# SCH_Octoslime_2022-08-05.net
KiCad netlist of a schematic drawn in EasyEDA
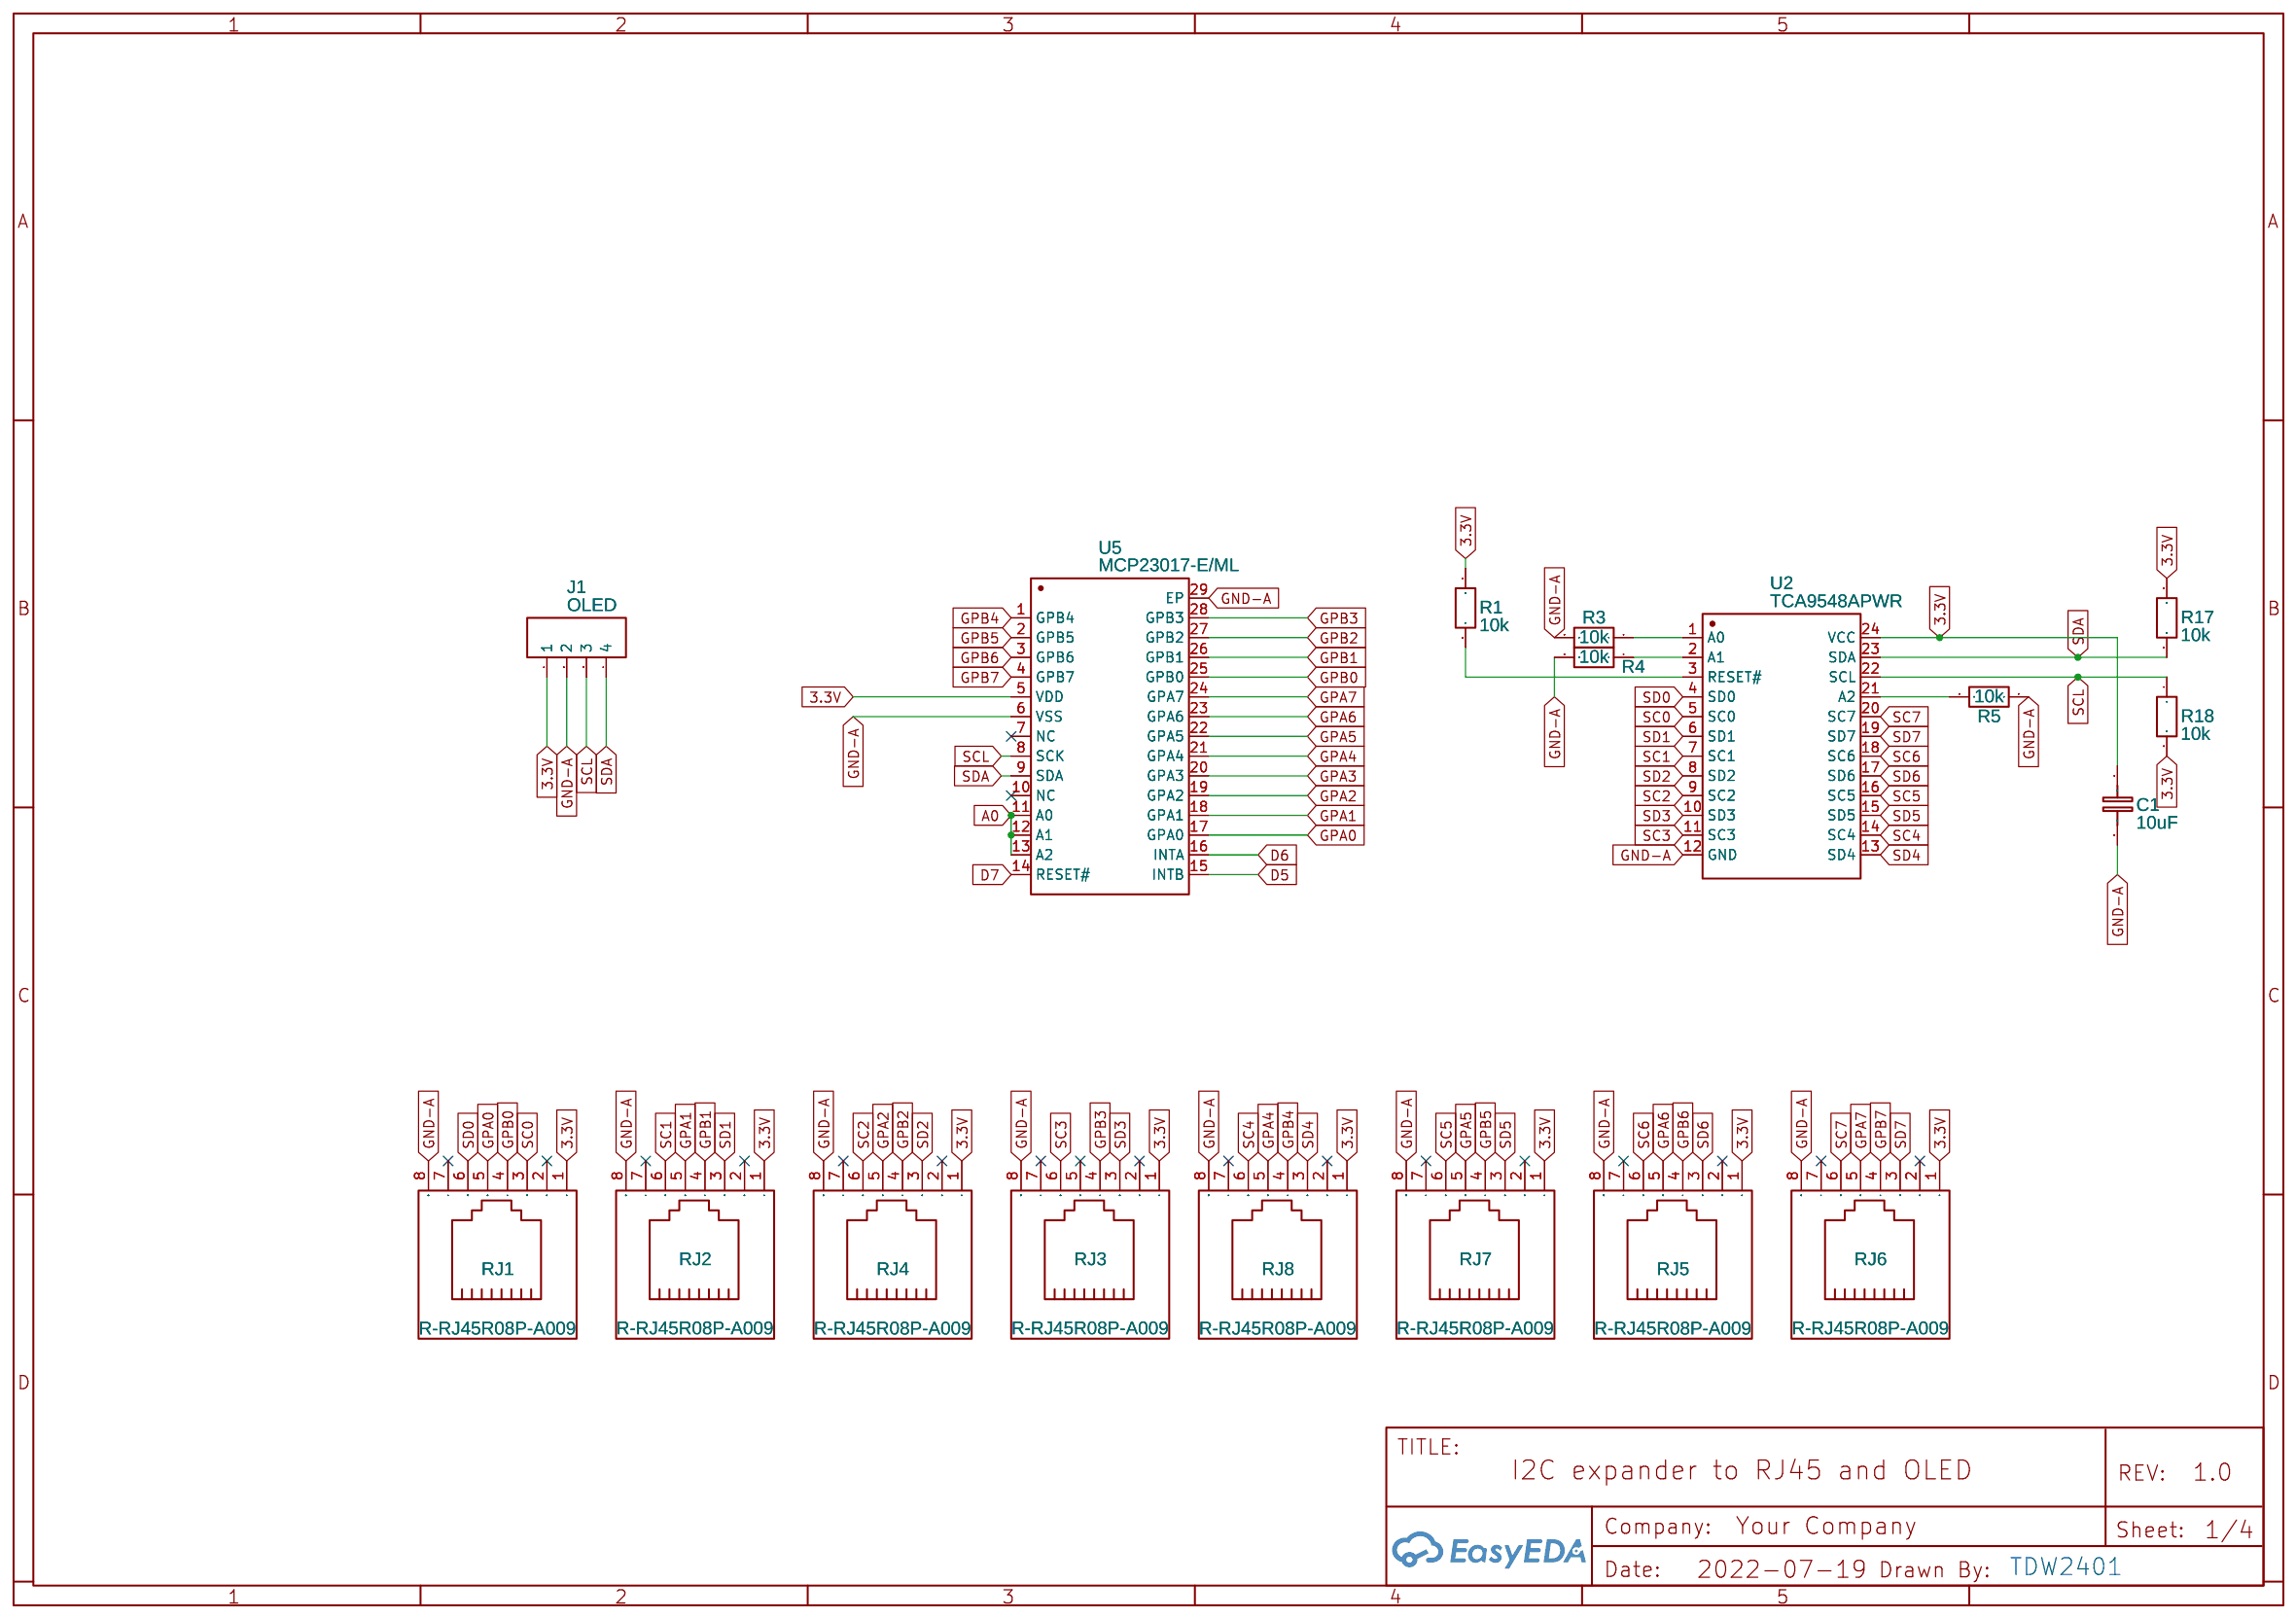
[diagram p0: I2C breakout and OLED]
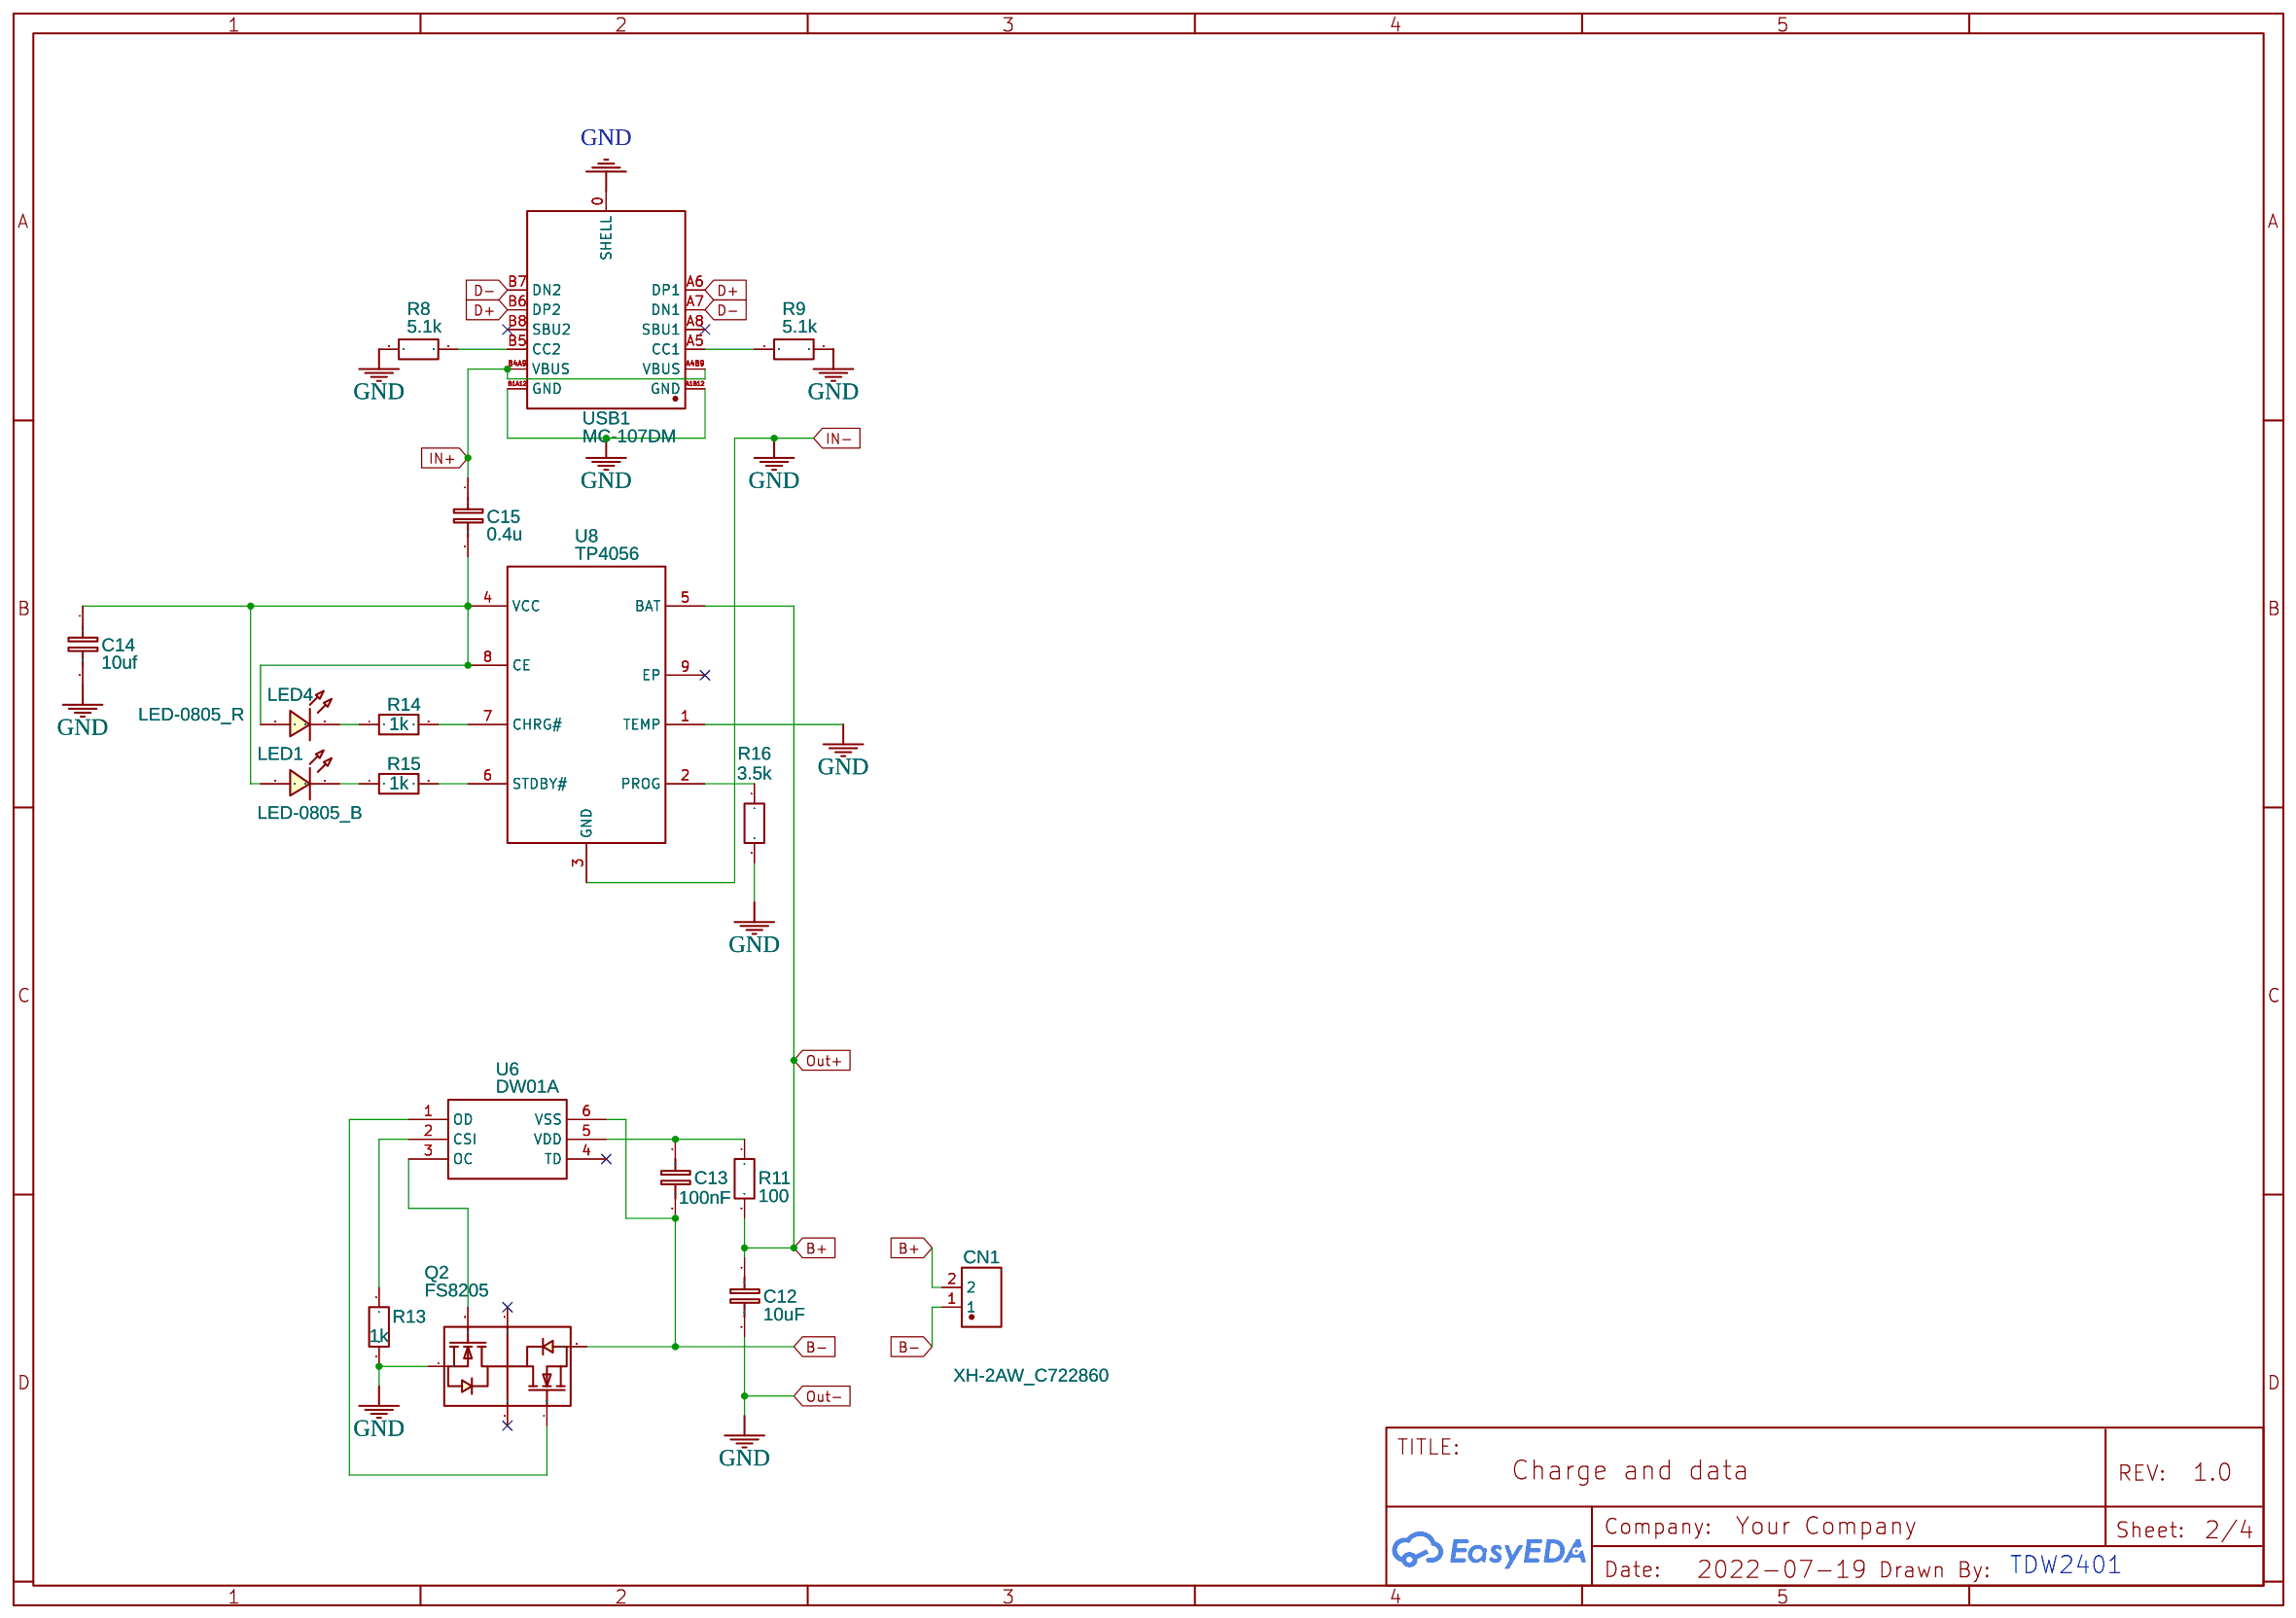
[diagram p1: Charge / data]
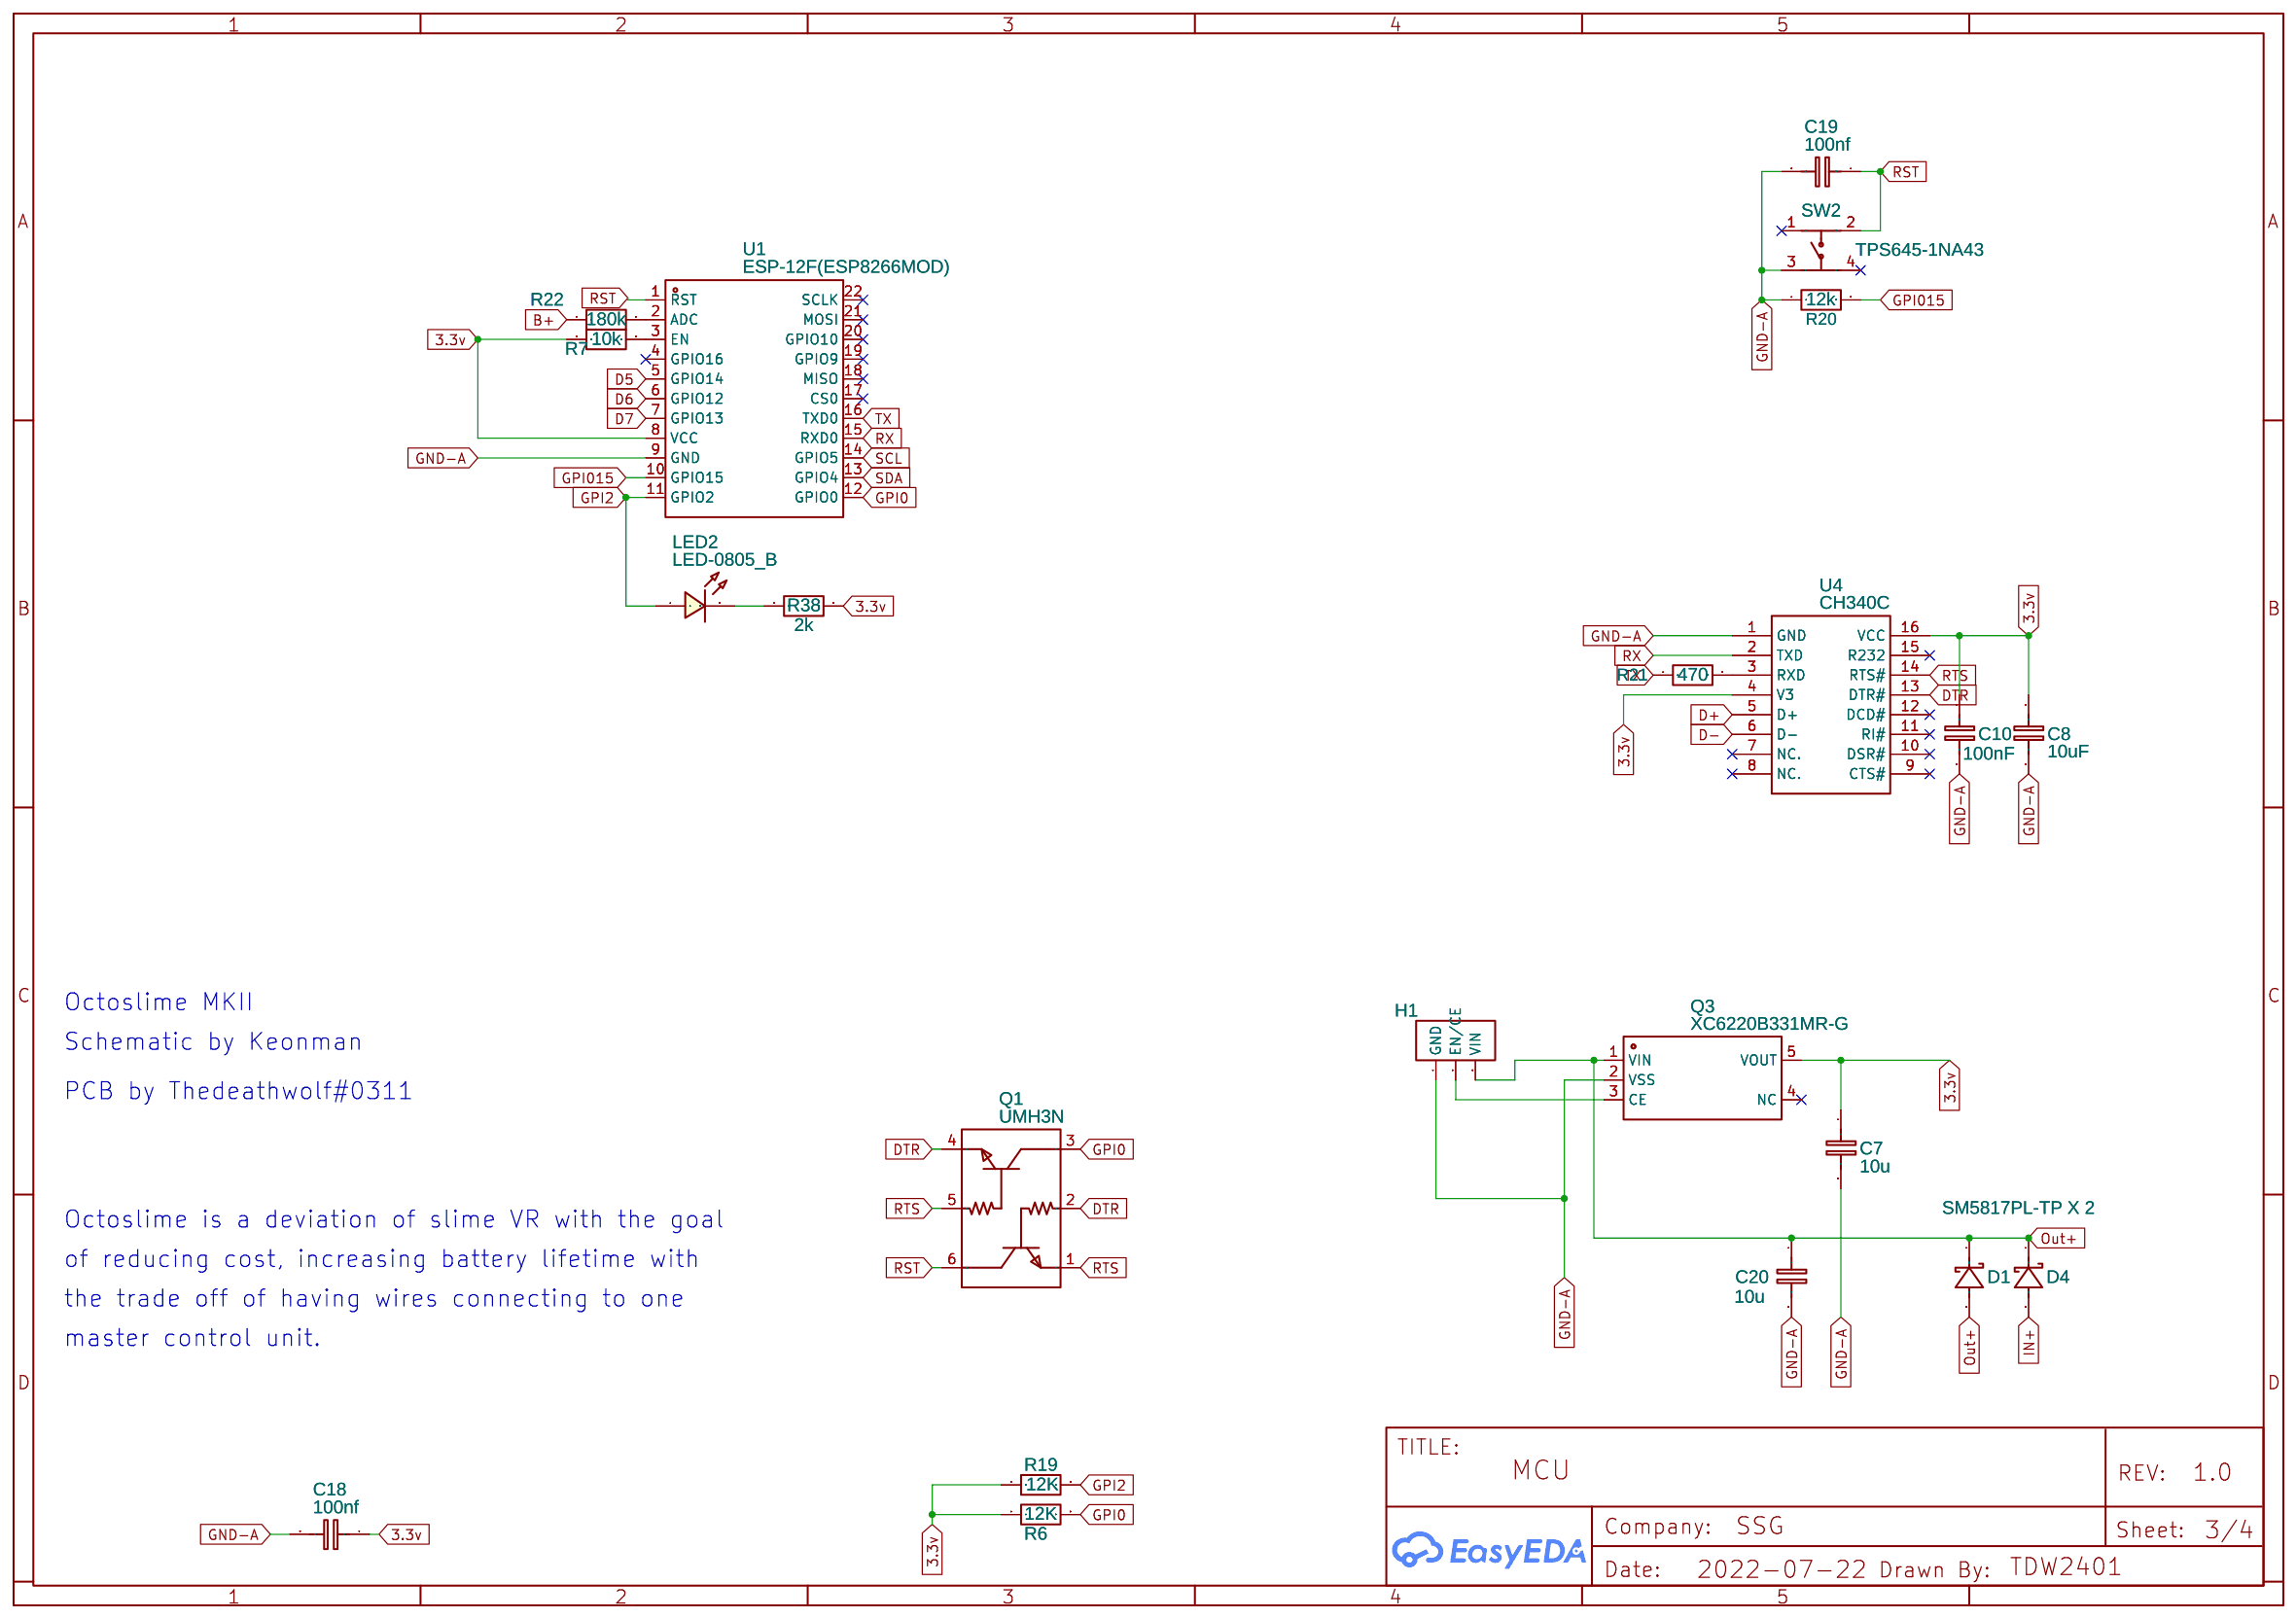
[diagram p2: MCU]
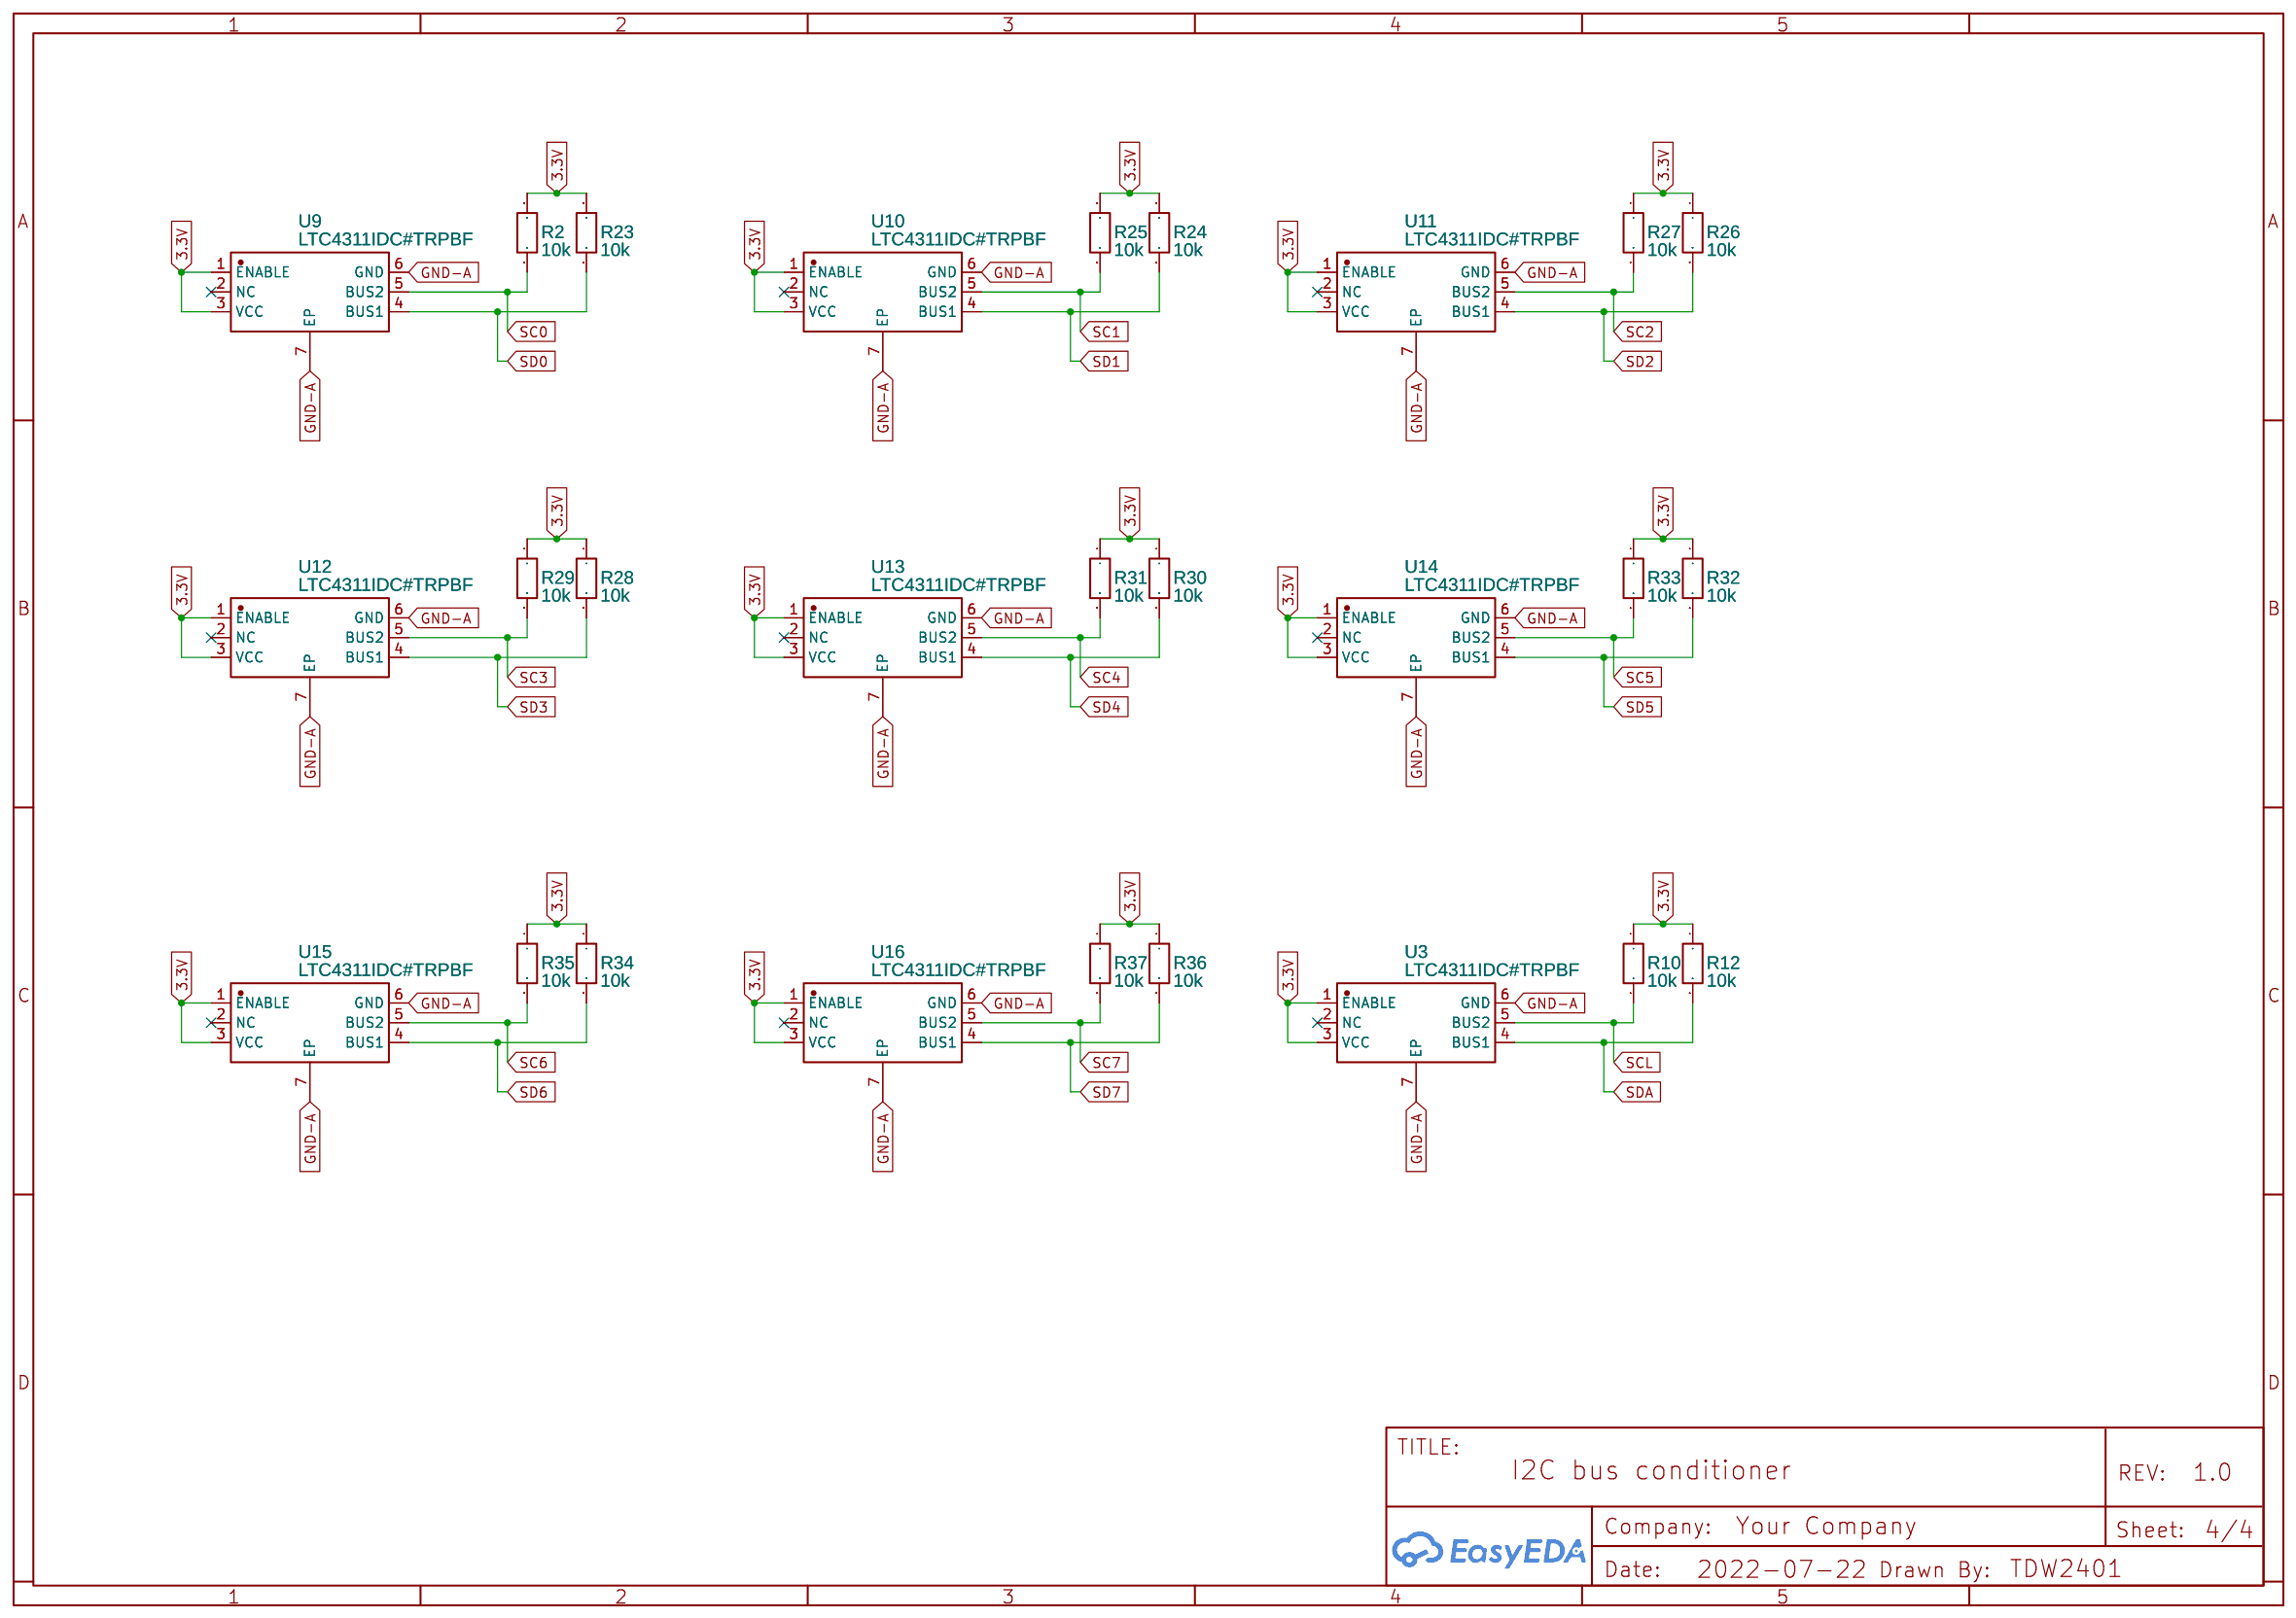
[diagram p3: I2C thing - ma - jigXC6220B331PR-G]

(export (version "E")
  (design (tool "Eeschema 10.0.6"))
  (components
    (comp (ref "C1") (value "10uF") (libsource (lib "") (part "C_0805_EU")))
    (comp (ref "J1")
      (value "OLED")
      (fields (field (name "BOM_Supplier Part") "C124378"))
      (libsource (lib "") (part "HDR-M-2.54_1x4"))
    )
    (comp (ref "R1") (value "10k") (libsource (lib "") (part "R_0805_EU")))
    (comp (ref "R3") (value "10k") (libsource (lib "") (part "R_0805_EU_1")))
    (comp (ref "R4") (value "10k") (libsource (lib "") (part "R_0805_EU_1")))
    (comp (ref "R5") (value "10k") (libsource (lib "") (part "R_0805_EU_1")))
    (comp (ref "R17") (value "10k") (libsource (lib "") (part "R_0805_EU")))
    (comp (ref "R18") (value "10k") (libsource (lib "") (part "R_0805_EU")))
    (comp (ref "RJ1")
      (value "R-RJ45R08P-A009")
      (fields (field (name "BOM_Supplier Part") "C2902700"))
      (libsource (lib "") (part "R-RJ45R08P-A009"))
    )
    (comp (ref "RJ2")
      (value "R-RJ45R08P-A009")
      (fields (field (name "BOM_Supplier Part") "C2902700"))
      (libsource (lib "") (part "R-RJ45R08P-A009"))
    )
    (comp (ref "RJ3")
      (value "R-RJ45R08P-A009")
      (fields (field (name "BOM_Supplier Part") "C2902700"))
      (libsource (lib "") (part "R-RJ45R08P-A009"))
    )
    (comp (ref "RJ4")
      (value "R-RJ45R08P-A009")
      (fields (field (name "BOM_Supplier Part") "C2902700"))
      (libsource (lib "") (part "R-RJ45R08P-A009"))
    )
    (comp (ref "RJ5")
      (value "R-RJ45R08P-A009")
      (fields (field (name "BOM_Supplier Part") "C2902700"))
      (libsource (lib "") (part "R-RJ45R08P-A009"))
    )
    (comp (ref "RJ6")
      (value "R-RJ45R08P-A009")
      (fields (field (name "BOM_Supplier Part") "C2902700"))
      (libsource (lib "") (part "R-RJ45R08P-A009"))
    )
    (comp (ref "RJ7")
      (value "R-RJ45R08P-A009")
      (fields (field (name "BOM_Supplier Part") "C2902700"))
      (libsource (lib "") (part "R-RJ45R08P-A009"))
    )
    (comp (ref "RJ8")
      (value "R-RJ45R08P-A009")
      (fields (field (name "BOM_Supplier Part") "C2902700"))
      (libsource (lib "") (part "R-RJ45R08P-A009"))
    )
    (comp (ref "U2")
      (value "TCA9548APWR")
      (fields (field (name "BOM_Supplier Part") "C130026"))
      (libsource (lib "") (part "TCA9548APWR"))
    )
    (comp (ref "U5")
      (value "MCP23017-E/ML")
      (fields (field (name "BOM_Supplier Part") "C639770"))
      (libsource (lib "") (part "MCP23017-E/ML"))
    )
    (comp (ref "C12") (value "10uF") (libsource (lib "") (part "C_0805_EU_1")))
    (comp (ref "C13") (value "100nF") (libsource (lib "") (part "C_0805_EU_1")))
    (comp (ref "C14") (value "10uf") (libsource (lib "") (part "C_0805_EU")))
    (comp (ref "C15") (value "0.4u") (libsource (lib "") (part "C_0805_EU_2")))
    (comp (ref "CN1")
      (value "XH-2AW_C722860")
      (fields (field (name "BOM_Manufacturer Part") "XH-2AW") (field (name "BOM_Supplier Part") "C722860"))
      (libsource (lib "") (part "XH-2AW_C722860"))
    )
    (comp (ref "LED1")
      (value "LED-0805_B")
      (fields
        (field (name "BOM_Manufacturer Part") "D-B080508B1-KS2")
        (field (name "BOM_Supplier Part") "C108412")
      )
      (libsource (lib "") (part "LED-0805_B"))
    )
    (comp (ref "LED4")
      (value "LED-0805_R")
      (fields
        (field (name "BOM_Manufacturer Part") "17-21SURC/S530-A3/TR8")
        (field (name "BOM_Supplier Part") "C72037")
      )
      (libsource (lib "") (part "LED-0805_R"))
    )
    (comp (ref "Q2")
      (value "FS8205")
      (fields (field (name "BOM_Supplier Part") "C32254"))
      (libsource (lib "") (part "FS8205"))
    )
    (comp (ref "R8") (value "5.1k") (libsource (lib "") (part "R_0805_EU_1")))
    (comp (ref "R9") (value "5.1k") (libsource (lib "") (part "R_0805_EU_1")))
    (comp (ref "R11") (value "100") (libsource (lib "") (part "R_0805_EU")))
    (comp (ref "R13") (value "1k") (libsource (lib "") (part "R_0805_EU")))
    (comp (ref "R14") (value "1k") (libsource (lib "") (part "R_0805_EU_1")))
    (comp (ref "R15") (value "1k") (libsource (lib "") (part "R_0805_EU_1")))
    (comp (ref "R16") (value "3.5k") (libsource (lib "") (part "R_0805_EU")))
    (comp (ref "U6")
      (value "DW01A")
      (fields (field (name "BOM_Supplier Part") "C85680"))
      (libsource (lib "") (part "DW01A"))
    )
    (comp (ref "U8")
      (value "TP4056")
      (fields (field (name "BOM_Supplier Part") "C16581"))
      (libsource (lib "") (part "TP4056"))
    )
    (comp (ref "USB1")
      (value "MC-107DM")
      (fields (field (name "BOM_Supplier Part") "C2874569"))
      (libsource (lib "") (part "MC-107DM"))
    )
    (comp (ref "C7") (value "10u") (libsource (lib "") (part "C_0805_EU")))
    (comp (ref "C8") (value "10uF") (libsource (lib "") (part "C_0805_EU")))
    (comp (ref "C10") (value "100nF") (libsource (lib "") (part "C_0805_EU")))
    (comp (ref "C18") (value "100nf") (libsource (lib "") (part "C_0805_EU_2")))
    (comp (ref "C19") (value "100nf") (libsource (lib "") (part "C_0805_EU_1")))
    (comp (ref "C20") (value "10u") (libsource (lib "") (part "C_0805_EU")))
    (comp (ref "D1")
      (value "SM5817PL-TP X 2")
      (fields
        (field (name "BOM_Manufacturer Part") "SM5817PL-TP")
        (field (name "BOM_Supplier Part") "C669022")
      )
      (libsource (lib "") (part "SM5817PL-TP"))
    )
    (comp (ref "D4")
      (value "SM5817PL-TP X 2")
      (fields
        (field (name "BOM_Manufacturer Part") "SM5817PL-TP")
        (field (name "BOM_Supplier Part") "C669022")
      )
      (libsource (lib "") (part "SM5817PL-TP"))
    )
    (comp (ref "H1")
      (value "HDR-F-2.54_1x3")
      (fields (field (name "BOM_Supplier Part") "C146690"))
      (libsource (lib "") (part "HDR-F-2.54_1x3"))
    )
    (comp (ref "LED2")
      (value "LED-0805_B")
      (fields
        (field (name "BOM_Manufacturer Part") "D-B080508B1-KS2")
        (field (name "BOM_Supplier Part") "C108412")
      )
      (libsource (lib "") (part "LED-0805_B"))
    )
    (comp (ref "Q1")
      (value "UMH3N")
      (fields (field (name "BOM_Supplier Part") "C62892"))
      (libsource (lib "") (part "UMH3N"))
    )
    (comp (ref "Q3")
      (value "XC6220B331MR-G")
      (fields (field (name "BOM_Supplier Part") "C86534"))
      (libsource (lib "") (part "XC6220B331MR-G"))
    )
    (comp (ref "R6") (value "12K") (libsource (lib "") (part "R_0805_EU")))
    (comp (ref "R7") (value "10k") (libsource (lib "") (part "R_0805_EU")))
    (comp (ref "R19") (value "12K") (libsource (lib "") (part "R_0805_EU")))
    (comp (ref "R20") (value "12k") (libsource (lib "") (part "R_0805_EU")))
    (comp (ref "R21") (value "470") (libsource (lib "") (part "R_0805_EU")))
    (comp (ref "R22") (value "180k") (libsource (lib "") (part "R_0805_EU")))
    (comp (ref "R38") (value "2k") (libsource (lib "") (part "R_0805_EU")))
    (comp (ref "SW2")
      (value "TPS645-1NA43")
      (fields (field (name "BOM_Supplier Part") "C2828575"))
      (libsource (lib "") (part "TPS645-1NA43"))
    )
    (comp (ref "U1")
      (value "ESP-12F(ESP8266MOD)")
      (fields (field (name "BOM_Supplier Part") "C82891"))
      (libsource (lib "") (part "ESP-12F(ESP8266MOD)"))
    )
    (comp (ref "U4")
      (value "CH340C")
      (fields (field (name "BOM_Supplier Part") "C84681"))
      (libsource (lib "") (part "CH340C"))
    )
    (comp (ref "R2") (value "10k") (libsource (lib "") (part "R_0805_EU")))
    (comp (ref "R10") (value "10k") (libsource (lib "") (part "R_0805_EU")))
    (comp (ref "R12") (value "10k") (libsource (lib "") (part "R_0805_EU")))
    (comp (ref "R23") (value "10k") (libsource (lib "") (part "R_0805_EU")))
    (comp (ref "R24") (value "10k") (libsource (lib "") (part "R_0805_EU")))
    (comp (ref "R25") (value "10k") (libsource (lib "") (part "R_0805_EU")))
    (comp (ref "R26") (value "10k") (libsource (lib "") (part "R_0805_EU")))
    (comp (ref "R27") (value "10k") (libsource (lib "") (part "R_0805_EU")))
    (comp (ref "R28") (value "10k") (libsource (lib "") (part "R_0805_EU")))
    (comp (ref "R29") (value "10k") (libsource (lib "") (part "R_0805_EU")))
    (comp (ref "R30") (value "10k") (libsource (lib "") (part "R_0805_EU")))
    (comp (ref "R31") (value "10k") (libsource (lib "") (part "R_0805_EU")))
    (comp (ref "R32") (value "10k") (libsource (lib "") (part "R_0805_EU")))
    (comp (ref "R33") (value "10k") (libsource (lib "") (part "R_0805_EU")))
    (comp (ref "R34") (value "10k") (libsource (lib "") (part "R_0805_EU")))
    (comp (ref "R35") (value "10k") (libsource (lib "") (part "R_0805_EU")))
    (comp (ref "R36") (value "10k") (libsource (lib "") (part "R_0805_EU")))
    (comp (ref "R37") (value "10k") (libsource (lib "") (part "R_0805_EU")))
    (comp (ref "U3")
      (value "LTC4311IDC#TRPBF")
      (fields (field (name "BOM_Supplier Part") "C688096"))
      (libsource (lib "") (part "LTC4311IDC#TRPBF"))
    )
    (comp (ref "U9")
      (value "LTC4311IDC#TRPBF")
      (fields (field (name "BOM_Supplier Part") "C688096"))
      (libsource (lib "") (part "LTC4311IDC#TRPBF"))
    )
    (comp (ref "U10")
      (value "LTC4311IDC#TRPBF")
      (fields (field (name "BOM_Supplier Part") "C688096"))
      (libsource (lib "") (part "LTC4311IDC#TRPBF"))
    )
    (comp (ref "U11")
      (value "LTC4311IDC#TRPBF")
      (fields (field (name "BOM_Supplier Part") "C688096"))
      (libsource (lib "") (part "LTC4311IDC#TRPBF"))
    )
    (comp (ref "U12")
      (value "LTC4311IDC#TRPBF")
      (fields (field (name "BOM_Supplier Part") "C688096"))
      (libsource (lib "") (part "LTC4311IDC#TRPBF"))
    )
    (comp (ref "U13")
      (value "LTC4311IDC#TRPBF")
      (fields (field (name "BOM_Supplier Part") "C688096"))
      (libsource (lib "") (part "LTC4311IDC#TRPBF"))
    )
    (comp (ref "U14")
      (value "LTC4311IDC#TRPBF")
      (fields (field (name "BOM_Supplier Part") "C688096"))
      (libsource (lib "") (part "LTC4311IDC#TRPBF"))
    )
    (comp (ref "U15")
      (value "LTC4311IDC#TRPBF")
      (fields (field (name "BOM_Supplier Part") "C688096"))
      (libsource (lib "") (part "LTC4311IDC#TRPBF"))
    )
    (comp (ref "U16")
      (value "LTC4311IDC#TRPBF")
      (fields (field (name "BOM_Supplier Part") "C688096"))
      (libsource (lib "") (part "LTC4311IDC#TRPBF"))
    )
  )
  (nets
    (net (code "1") (name "3.3V") (class "Default")
      (node (ref "C1") (pin "1") (pinfunction "1_1") (pintype "unspecified"))
      (node (ref "J1") (pin "1") (pinfunction "1_1") (pintype "unspecified"))
      (node (ref "R1") (pin "1") (pinfunction "1_1") (pintype "unspecified"))
      (node (ref "R10") (pin "1") (pinfunction "1_1") (pintype "unspecified"))
      (node (ref "R12") (pin "1") (pinfunction "1_1") (pintype "unspecified"))
      (node (ref "R17") (pin "1") (pinfunction "1_1") (pintype "unspecified"))
      (node (ref "R18") (pin "2") (pinfunction "2_2") (pintype "unspecified"))
      (node (ref "R2") (pin "1") (pinfunction "1_1") (pintype "unspecified"))
      (node (ref "R23") (pin "1") (pinfunction "1_1") (pintype "unspecified"))
      (node (ref "R24") (pin "1") (pinfunction "1_1") (pintype "unspecified"))
      (node (ref "R25") (pin "1") (pinfunction "1_1") (pintype "unspecified"))
      (node (ref "R26") (pin "1") (pinfunction "1_1") (pintype "unspecified"))
      (node (ref "R27") (pin "1") (pinfunction "1_1") (pintype "unspecified"))
      (node (ref "R28") (pin "1") (pinfunction "1_1") (pintype "unspecified"))
      (node (ref "R29") (pin "1") (pinfunction "1_1") (pintype "unspecified"))
      (node (ref "R30") (pin "1") (pinfunction "1_1") (pintype "unspecified"))
      (node (ref "R31") (pin "1") (pinfunction "1_1") (pintype "unspecified"))
      (node (ref "R32") (pin "1") (pinfunction "1_1") (pintype "unspecified"))
      (node (ref "R33") (pin "1") (pinfunction "1_1") (pintype "unspecified"))
      (node (ref "R34") (pin "1") (pinfunction "1_1") (pintype "unspecified"))
      (node (ref "R35") (pin "1") (pinfunction "1_1") (pintype "unspecified"))
      (node (ref "R36") (pin "1") (pinfunction "1_1") (pintype "unspecified"))
      (node (ref "R37") (pin "1") (pinfunction "1_1") (pintype "unspecified"))
      (node (ref "RJ1") (pin "1") (pinfunction "1_1") (pintype "unspecified"))
      (node (ref "RJ2") (pin "1") (pinfunction "1_1") (pintype "unspecified"))
      (node (ref "RJ3") (pin "1") (pinfunction "1_1") (pintype "unspecified"))
      (node (ref "RJ4") (pin "1") (pinfunction "1_1") (pintype "unspecified"))
      (node (ref "RJ5") (pin "1") (pinfunction "1_1") (pintype "unspecified"))
      (node (ref "RJ6") (pin "1") (pinfunction "1_1") (pintype "unspecified"))
      (node (ref "RJ7") (pin "1") (pinfunction "1_1") (pintype "unspecified"))
      (node (ref "RJ8") (pin "1") (pinfunction "1_1") (pintype "unspecified"))
      (node (ref "U10") (pin "1") (pinfunction "ENABLE_1") (pintype "unspecified"))
      (node (ref "U10") (pin "3") (pinfunction "VCC_3") (pintype "unspecified"))
      (node (ref "U11") (pin "1") (pinfunction "ENABLE_1") (pintype "unspecified"))
      (node (ref "U11") (pin "3") (pinfunction "VCC_3") (pintype "unspecified"))
      (node (ref "U12") (pin "1") (pinfunction "ENABLE_1") (pintype "unspecified"))
      (node (ref "U12") (pin "3") (pinfunction "VCC_3") (pintype "unspecified"))
      (node (ref "U13") (pin "1") (pinfunction "ENABLE_1") (pintype "unspecified"))
      (node (ref "U13") (pin "3") (pinfunction "VCC_3") (pintype "unspecified"))
      (node (ref "U14") (pin "1") (pinfunction "ENABLE_1") (pintype "unspecified"))
      (node (ref "U14") (pin "3") (pinfunction "VCC_3") (pintype "unspecified"))
      (node (ref "U15") (pin "1") (pinfunction "ENABLE_1") (pintype "unspecified"))
      (node (ref "U15") (pin "3") (pinfunction "VCC_3") (pintype "unspecified"))
      (node (ref "U16") (pin "1") (pinfunction "ENABLE_1") (pintype "unspecified"))
      (node (ref "U16") (pin "3") (pinfunction "VCC_3") (pintype "unspecified"))
      (node (ref "U2") (pin "24") (pinfunction "VCC_24") (pintype "unspecified"))
      (node (ref "U3") (pin "1") (pinfunction "ENABLE_1") (pintype "unspecified"))
      (node (ref "U3") (pin "3") (pinfunction "VCC_3") (pintype "unspecified"))
      (node (ref "U5") (pin "5") (pinfunction "VDD_5") (pintype "unspecified"))
      (node (ref "U9") (pin "1") (pinfunction "ENABLE_1") (pintype "unspecified"))
      (node (ref "U9") (pin "3") (pinfunction "VCC_3") (pintype "unspecified"))
    )
    (net (code "2") (name "3.3v") (class "Default")
      (node (ref "C10") (pin "1") (pinfunction "1_1") (pintype "unspecified"))
      (node (ref "C18") (pin "1") (pinfunction "1_1") (pintype "unspecified"))
      (node (ref "C7") (pin "1") (pinfunction "1_1") (pintype "unspecified"))
      (node (ref "C8") (pin "1") (pinfunction "1_1") (pintype "unspecified"))
      (node (ref "Q3") (pin "5") (pinfunction "VOUT_5") (pintype "unspecified"))
      (node (ref "R19") (pin "1") (pinfunction "1_1") (pintype "unspecified"))
      (node (ref "R38") (pin "2") (pinfunction "2_2") (pintype "unspecified"))
      (node (ref "R6") (pin "1") (pinfunction "1_1") (pintype "unspecified"))
      (node (ref "R7") (pin "1") (pinfunction "1_1") (pintype "unspecified"))
      (node (ref "U1") (pin "8") (pinfunction "VCC_8") (pintype "unspecified"))
      (node (ref "U4") (pin "16") (pinfunction "VCC_16") (pintype "unspecified"))
      (node (ref "U4") (pin "4") (pinfunction "V3_4") (pintype "unspecified"))
    )
    (net (code "3") (name "A0") (class "Default")
      (node (ref "U5") (pin "11") (pinfunction "A0_11") (pintype "unspecified"))
      (node (ref "U5") (pin "12") (pinfunction "A1_12") (pintype "unspecified"))
      (node (ref "U5") (pin "13") (pinfunction "A2_13") (pintype "unspecified"))
    )
    (net (code "4") (name "B+") (class "Default")
      (node (ref "C12") (pin "1") (pinfunction "1_1") (pintype "unspecified"))
      (node (ref "C20") (pin "1") (pinfunction "1_1") (pintype "unspecified"))
      (node (ref "CN1") (pin "2") (pinfunction "2_2") (pintype "unspecified"))
      (node (ref "D1") (pin "1") (pinfunction "C_1") (pintype "unspecified"))
      (node (ref "D1") (pin "2") (pinfunction "A_2") (pintype "unspecified"))
      (node (ref "D4") (pin "1") (pinfunction "C_1") (pintype "unspecified"))
      (node (ref "H1") (pin "3") (pinfunction "VIN_3") (pintype "input"))
      (node (ref "Q3") (pin "1") (pinfunction "VIN_1") (pintype "unspecified"))
      (node (ref "R11") (pin "2") (pinfunction "2_2") (pintype "unspecified"))
      (node (ref "R22") (pin "1") (pinfunction "1_1") (pintype "unspecified"))
      (node (ref "U8") (pin "5") (pinfunction "BAT_5") (pintype "unspecified"))
    )
    (net (code "5") (name "B-") (class "Default")
      (node (ref "C13") (pin "2") (pinfunction "2_2") (pintype "unspecified"))
      (node (ref "CN1") (pin "1") (pinfunction "1_1") (pintype "unspecified"))
      (node (ref "Q2") (pin "3") (pinfunction "S2_3") (pintype "unspecified"))
      (node (ref "U6") (pin "6") (pinfunction "VSS_6") (pintype "unspecified"))
    )
    (net (code "6") (name "D+") (class "Default")
      (node (ref "U4") (pin "5") (pinfunction "D+_5") (pintype "unspecified"))
      (node (ref "USB1") (pin "A6") (pinfunction "DP1_A6") (pintype "unspecified"))
      (node (ref "USB1") (pin "B6") (pinfunction "DP2_B6") (pintype "unspecified"))
    )
    (net (code "7") (name "D-") (class "Default")
      (node (ref "U4") (pin "6") (pinfunction "D-_6") (pintype "unspecified"))
      (node (ref "USB1") (pin "A7") (pinfunction "DN1_A7") (pintype "unspecified"))
      (node (ref "USB1") (pin "B7") (pinfunction "DN2_B7") (pintype "unspecified"))
    )
    (net (code "8") (name "D5") (class "Default")
      (node (ref "U1") (pin "5") (pinfunction "GPIO14_5") (pintype "unspecified"))
      (node (ref "U5") (pin "15") (pinfunction "INTB_15") (pintype "unspecified"))
    )
    (net (code "9") (name "D6") (class "Default")
      (node (ref "U1") (pin "6") (pinfunction "GPIO12_6") (pintype "unspecified"))
      (node (ref "U5") (pin "16") (pinfunction "INTA_16") (pintype "unspecified"))
    )
    (net (code "10") (name "D7") (class "Default")
      (node (ref "U1") (pin "7") (pinfunction "GPIO13_7") (pintype "unspecified"))
      (node (ref "U5") (pin "14") (pinfunction "RESET#_14") (pintype "unspecified"))
    )
    (net (code "11") (name "DTR") (class "Default")
      (node (ref "Q1") (pin "2") (pinfunction "B_2") (pintype "unspecified"))
      (node (ref "Q1") (pin "4") (pinfunction "E_4") (pintype "unspecified"))
      (node (ref "U4") (pin "13") (pinfunction "DTR#_13") (pintype "unspecified"))
    )
    (net (code "12") (name "GND-A") (class "Default")
      (node (ref "C1") (pin "2") (pinfunction "2_2") (pintype "unspecified"))
      (node (ref "C10") (pin "2") (pinfunction "2_2") (pintype "unspecified"))
      (node (ref "C18") (pin "2") (pinfunction "2_2") (pintype "unspecified"))
      (node (ref "C19") (pin "2") (pinfunction "2_2") (pintype "unspecified"))
      (node (ref "C20") (pin "2") (pinfunction "2_2") (pintype "unspecified"))
      (node (ref "C7") (pin "2") (pinfunction "2_2") (pintype "unspecified"))
      (node (ref "C8") (pin "2") (pinfunction "2_2") (pintype "unspecified"))
      (node (ref "H1") (pin "1") (pinfunction "GND_1") (pintype "input"))
      (node (ref "J1") (pin "2") (pinfunction "2_2") (pintype "unspecified"))
      (node (ref "Q3") (pin "2") (pinfunction "VSS_2") (pintype "unspecified"))
      (node (ref "R20") (pin "1") (pinfunction "1_1") (pintype "unspecified"))
      (node (ref "R3") (pin "2") (pinfunction "2_2") (pintype "unspecified"))
      (node (ref "R4") (pin "2") (pinfunction "2_2") (pintype "unspecified"))
      (node (ref "R5") (pin "1") (pinfunction "1_1") (pintype "unspecified"))
      (node (ref "RJ1") (pin "8") (pinfunction "8_8") (pintype "unspecified"))
      (node (ref "RJ2") (pin "8") (pinfunction "8_8") (pintype "unspecified"))
      (node (ref "RJ3") (pin "8") (pinfunction "8_8") (pintype "unspecified"))
      (node (ref "RJ4") (pin "8") (pinfunction "8_8") (pintype "unspecified"))
      (node (ref "RJ5") (pin "8") (pinfunction "8_8") (pintype "unspecified"))
      (node (ref "RJ6") (pin "8") (pinfunction "8_8") (pintype "unspecified"))
      (node (ref "RJ7") (pin "8") (pinfunction "8_8") (pintype "unspecified"))
      (node (ref "RJ8") (pin "8") (pinfunction "8_8") (pintype "unspecified"))
      (node (ref "SW2") (pin "3") (pinfunction "3_3") (pintype "unspecified"))
      (node (ref "U1") (pin "9") (pinfunction "GND_9") (pintype "unspecified"))
      (node (ref "U10") (pin "6") (pinfunction "GND_6") (pintype "unspecified"))
      (node (ref "U10") (pin "7") (pinfunction "EP_7") (pintype "unspecified"))
      (node (ref "U11") (pin "6") (pinfunction "GND_6") (pintype "unspecified"))
      (node (ref "U11") (pin "7") (pinfunction "EP_7") (pintype "unspecified"))
      (node (ref "U12") (pin "6") (pinfunction "GND_6") (pintype "unspecified"))
      (node (ref "U12") (pin "7") (pinfunction "EP_7") (pintype "unspecified"))
      (node (ref "U13") (pin "6") (pinfunction "GND_6") (pintype "unspecified"))
      (node (ref "U13") (pin "7") (pinfunction "EP_7") (pintype "unspecified"))
      (node (ref "U14") (pin "6") (pinfunction "GND_6") (pintype "unspecified"))
      (node (ref "U14") (pin "7") (pinfunction "EP_7") (pintype "unspecified"))
      (node (ref "U15") (pin "6") (pinfunction "GND_6") (pintype "unspecified"))
      (node (ref "U15") (pin "7") (pinfunction "EP_7") (pintype "unspecified"))
      (node (ref "U16") (pin "6") (pinfunction "GND_6") (pintype "unspecified"))
      (node (ref "U16") (pin "7") (pinfunction "EP_7") (pintype "unspecified"))
      (node (ref "U2") (pin "12") (pinfunction "GND_12") (pintype "unspecified"))
      (node (ref "U3") (pin "6") (pinfunction "GND_6") (pintype "unspecified"))
      (node (ref "U3") (pin "7") (pinfunction "EP_7") (pintype "unspecified"))
      (node (ref "U4") (pin "1") (pinfunction "GND_1") (pintype "unspecified"))
      (node (ref "U5") (pin "29") (pinfunction "EP_29") (pintype "unspecified"))
      (node (ref "U5") (pin "6") (pinfunction "VSS_6") (pintype "unspecified"))
      (node (ref "U9") (pin "6") (pinfunction "GND_6") (pintype "unspecified"))
      (node (ref "U9") (pin "7") (pinfunction "EP_7") (pintype "unspecified"))
    )
    (net (code "13") (name "GPA0") (class "Default")
      (node (ref "RJ1") (pin "5") (pinfunction "5_5") (pintype "unspecified"))
      (node (ref "U5") (pin "17") (pinfunction "GPA0_17") (pintype "unspecified"))
    )
    (net (code "14") (name "GPA1") (class "Default")
      (node (ref "RJ2") (pin "5") (pinfunction "5_5") (pintype "unspecified"))
      (node (ref "U5") (pin "18") (pinfunction "GPA1_18") (pintype "unspecified"))
    )
    (net (code "15") (name "GPA2") (class "Default")
      (node (ref "RJ4") (pin "5") (pinfunction "5_5") (pintype "unspecified"))
      (node (ref "U5") (pin "19") (pinfunction "GPA2_19") (pintype "unspecified"))
    )
    (net (code "16") (name "GPA3") (class "Default")
      (node (ref "U5") (pin "20") (pinfunction "GPA3_20") (pintype "unspecified"))
    )
    (net (code "17") (name "GPA4") (class "Default")
      (node (ref "RJ8") (pin "5") (pinfunction "5_5") (pintype "unspecified"))
      (node (ref "U5") (pin "21") (pinfunction "GPA4_21") (pintype "unspecified"))
    )
    (net (code "18") (name "GPA5") (class "Default")
      (node (ref "RJ7") (pin "5") (pinfunction "5_5") (pintype "unspecified"))
      (node (ref "U5") (pin "22") (pinfunction "GPA5_22") (pintype "unspecified"))
    )
    (net (code "19") (name "GPA6") (class "Default")
      (node (ref "RJ5") (pin "5") (pinfunction "5_5") (pintype "unspecified"))
      (node (ref "U5") (pin "23") (pinfunction "GPA6_23") (pintype "unspecified"))
    )
    (net (code "20") (name "GPA7") (class "Default")
      (node (ref "RJ6") (pin "5") (pinfunction "5_5") (pintype "unspecified"))
      (node (ref "U5") (pin "24") (pinfunction "GPA7_24") (pintype "unspecified"))
    )
    (net (code "21") (name "GPB0") (class "Default")
      (node (ref "RJ1") (pin "4") (pinfunction "4_4") (pintype "unspecified"))
      (node (ref "U5") (pin "25") (pinfunction "GPB0_25") (pintype "unspecified"))
    )
    (net (code "22") (name "GPB1") (class "Default")
      (node (ref "RJ2") (pin "4") (pinfunction "4_4") (pintype "unspecified"))
      (node (ref "U5") (pin "26") (pinfunction "GPB1_26") (pintype "unspecified"))
    )
    (net (code "23") (name "GPB2") (class "Default")
      (node (ref "RJ4") (pin "4") (pinfunction "4_4") (pintype "unspecified"))
      (node (ref "U5") (pin "27") (pinfunction "GPB2_27") (pintype "unspecified"))
    )
    (net (code "24") (name "GPB3") (class "Default")
      (node (ref "RJ3") (pin "4") (pinfunction "4_4") (pintype "unspecified"))
      (node (ref "U5") (pin "28") (pinfunction "GPB3_28") (pintype "unspecified"))
    )
    (net (code "25") (name "GPB4") (class "Default")
      (node (ref "RJ8") (pin "4") (pinfunction "4_4") (pintype "unspecified"))
      (node (ref "U5") (pin "1") (pinfunction "GPB4_1") (pintype "unspecified"))
    )
    (net (code "26") (name "GPB5") (class "Default")
      (node (ref "RJ7") (pin "4") (pinfunction "4_4") (pintype "unspecified"))
      (node (ref "U5") (pin "2") (pinfunction "GPB5_2") (pintype "unspecified"))
    )
    (net (code "27") (name "GPB6") (class "Default")
      (node (ref "RJ5") (pin "4") (pinfunction "4_4") (pintype "unspecified"))
      (node (ref "U5") (pin "3") (pinfunction "GPB6_3") (pintype "unspecified"))
    )
    (net (code "28") (name "GPB7") (class "Default")
      (node (ref "RJ6") (pin "4") (pinfunction "4_4") (pintype "unspecified"))
      (node (ref "U5") (pin "4") (pinfunction "GPB7_4") (pintype "unspecified"))
    )
    (net (code "29") (name "GPI0") (class "Default")
      (node (ref "Q1") (pin "3") (pinfunction "C_3") (pintype "unspecified"))
      (node (ref "R6") (pin "2") (pinfunction "2_2") (pintype "unspecified"))
      (node (ref "U1") (pin "12") (pinfunction "GPIO0_12") (pintype "unspecified"))
    )
    (net (code "30") (name "GPI2") (class "Default")
      (node (ref "LED2") (pin "1") (pinfunction "1_1") (pintype "unspecified"))
      (node (ref "R19") (pin "2") (pinfunction "2_2") (pintype "unspecified"))
      (node (ref "U1") (pin "11") (pinfunction "GPIO2_11") (pintype "unspecified"))
    )
    (net (code "31") (name "GPI015") (class "Default")
      (node (ref "R20") (pin "2") (pinfunction "2_2") (pintype "unspecified"))
      (node (ref "U1") (pin "10") (pinfunction "GPIO15_10") (pintype "unspecified"))
    )
    (net (code "32") (name "IN+") (class "Default")
      (node (ref "C15") (pin "1") (pinfunction "1_1") (pintype "unspecified"))
      (node (ref "D4") (pin "2") (pinfunction "A_2") (pintype "unspecified"))
      (node (ref "USB1") (pin "A4B9") (pinfunction "VBUS_A4B9") (pintype "unspecified"))
      (node (ref "USB1") (pin "B4A9") (pinfunction "VBUS_B4A9") (pintype "unspecified"))
    )
    (net (code "33") (name "IN-") (class "Default")
      (node (ref "C12") (pin "2") (pinfunction "2_2") (pintype "unspecified"))
      (node (ref "C14") (pin "2") (pinfunction "2_2") (pintype "unspecified"))
      (node (ref "Q2") (pin "1") (pinfunction "S1_1") (pintype "unspecified"))
      (node (ref "R13") (pin "2") (pinfunction "2_2") (pintype "unspecified"))
      (node (ref "R16") (pin "2") (pinfunction "2_2") (pintype "unspecified"))
      (node (ref "R8") (pin "1") (pinfunction "1_1") (pintype "unspecified"))
      (node (ref "R9") (pin "2") (pinfunction "2_2") (pintype "unspecified"))
      (node (ref "U8") (pin "1") (pinfunction "TEMP_1") (pintype "unspecified"))
      (node (ref "U8") (pin "3") (pinfunction "GND_3") (pintype "unspecified"))
      (node (ref "USB1") (pin "0") (pinfunction "SHELL_0") (pintype "unspecified"))
      (node (ref "USB1") (pin "A1B12") (pinfunction "GND_A1B12") (pintype "unspecified"))
      (node (ref "USB1") (pin "B1A12") (pinfunction "GND_B1A12") (pintype "unspecified"))
    )
    (net (code "34") (name "Net-(H1-EN{slash}CE)") (class "Default")
      (node (ref "H1") (pin "2") (pinfunction "EN/CE_2") (pintype "input"))
      (node (ref "Q3") (pin "3") (pinfunction "CE_3") (pintype "unspecified"))
    )
    (net (code "35") (name "Net-(LED1-Pad2)") (class "Default")
      (node (ref "LED1") (pin "2") (pinfunction "2_2") (pintype "unspecified"))
      (node (ref "R15") (pin "1") (pinfunction "1_1") (pintype "unspecified"))
    )
    (net (code "36") (name "Net-(LED2-Pad2)") (class "Default")
      (node (ref "LED2") (pin "2") (pinfunction "2_2") (pintype "unspecified"))
      (node (ref "R38") (pin "1") (pinfunction "1_1") (pintype "unspecified"))
    )
    (net (code "37") (name "Net-(LED4-Pad2)") (class "Default")
      (node (ref "LED4") (pin "2") (pinfunction "2_2") (pintype "unspecified"))
      (node (ref "R14") (pin "1") (pinfunction "1_1") (pintype "unspecified"))
    )
    (net (code "38") (name "Net-(Q2-G1)") (class "Default")
      (node (ref "Q2") (pin "6") (pinfunction "G1_6") (pintype "unspecified"))
      (node (ref "U6") (pin "3") (pinfunction "OC_3") (pintype "unspecified"))
    )
    (net (code "39") (name "Net-(Q2-G2)") (class "Default")
      (node (ref "Q2") (pin "4") (pinfunction "G2_4") (pintype "unspecified"))
      (node (ref "U6") (pin "1") (pinfunction "OD_1") (pintype "unspecified"))
    )
    (net (code "40") (name "Net-(U1-ADC)") (class "Default")
      (node (ref "R22") (pin "2") (pinfunction "2_2") (pintype "unspecified"))
      (node (ref "U1") (pin "2") (pinfunction "ADC_2") (pintype "unspecified"))
    )
    (net (code "41") (name "Net-(U1-EN)") (class "Default")
      (node (ref "R7") (pin "2") (pinfunction "2_2") (pintype "unspecified"))
      (node (ref "U1") (pin "3") (pinfunction "EN_3") (pintype "unspecified"))
    )
    (net (code "42") (name "Net-(U2-A0)") (class "Default")
      (node (ref "R3") (pin "1") (pinfunction "1_1") (pintype "unspecified"))
      (node (ref "U2") (pin "1") (pinfunction "A0_1") (pintype "unspecified"))
    )
    (net (code "43") (name "Net-(U2-A1)") (class "Default")
      (node (ref "R4") (pin "1") (pinfunction "1_1") (pintype "unspecified"))
      (node (ref "U2") (pin "2") (pinfunction "A1_2") (pintype "unspecified"))
    )
    (net (code "44") (name "Net-(U2-A2)") (class "Default")
      (node (ref "R5") (pin "2") (pinfunction "2_2") (pintype "unspecified"))
      (node (ref "U2") (pin "21") (pinfunction "A2_21") (pintype "unspecified"))
    )
    (net (code "45") (name "Net-(U2-RESET#)") (class "Default")
      (node (ref "R1") (pin "2") (pinfunction "2_2") (pintype "unspecified"))
      (node (ref "U2") (pin "3") (pinfunction "RESET#_3") (pintype "unspecified"))
    )
    (net (code "46") (name "Net-(U4-RXD)") (class "Default")
      (node (ref "R21") (pin "2") (pinfunction "2_2") (pintype "unspecified"))
      (node (ref "U4") (pin "3") (pinfunction "RXD_3") (pintype "unspecified"))
    )
    (net (code "47") (name "Net-(U6-CSI)") (class "Default")
      (node (ref "R13") (pin "1") (pinfunction "1_1") (pintype "unspecified"))
      (node (ref "U6") (pin "2") (pinfunction "CSI_2") (pintype "unspecified"))
    )
    (net (code "48") (name "Net-(U6-VDD)") (class "Default")
      (node (ref "C13") (pin "1") (pinfunction "1_1") (pintype "unspecified"))
      (node (ref "R11") (pin "1") (pinfunction "1_1") (pintype "unspecified"))
      (node (ref "U6") (pin "5") (pinfunction "VDD_5") (pintype "unspecified"))
    )
    (net (code "49") (name "Net-(U8-CE)") (class "Default")
      (node (ref "C14") (pin "1") (pinfunction "1_1") (pintype "unspecified"))
      (node (ref "C15") (pin "2") (pinfunction "2_2") (pintype "unspecified"))
      (node (ref "LED1") (pin "1") (pinfunction "1_1") (pintype "unspecified"))
      (node (ref "LED4") (pin "1") (pinfunction "1_1") (pintype "unspecified"))
      (node (ref "U8") (pin "4") (pinfunction "VCC_4") (pintype "unspecified"))
      (node (ref "U8") (pin "8") (pinfunction "CE_8") (pintype "unspecified"))
    )
    (net (code "50") (name "Net-(U8-CHRG#)") (class "Default")
      (node (ref "R14") (pin "2") (pinfunction "2_2") (pintype "unspecified"))
      (node (ref "U8") (pin "7") (pinfunction "CHRG#_7") (pintype "unspecified"))
    )
    (net (code "51") (name "Net-(U8-PROG)") (class "Default")
      (node (ref "R16") (pin "1") (pinfunction "1_1") (pintype "unspecified"))
      (node (ref "U8") (pin "2") (pinfunction "PROG_2") (pintype "unspecified"))
    )
    (net (code "52") (name "Net-(U8-STDBY#)") (class "Default")
      (node (ref "R15") (pin "2") (pinfunction "2_2") (pintype "unspecified"))
      (node (ref "U8") (pin "6") (pinfunction "STDBY#_6") (pintype "unspecified"))
    )
    (net (code "53") (name "Net-(USB1-CC1)") (class "Default")
      (node (ref "R9") (pin "1") (pinfunction "1_1") (pintype "unspecified"))
      (node (ref "USB1") (pin "A5") (pinfunction "CC1_A5") (pintype "unspecified"))
    )
    (net (code "54") (name "Net-(USB1-CC2)") (class "Default")
      (node (ref "R8") (pin "2") (pinfunction "2_2") (pintype "unspecified"))
      (node (ref "USB1") (pin "B5") (pinfunction "CC2_B5") (pintype "unspecified"))
    )
    (net (code "55") (name "RST") (class "Default")
      (node (ref "C19") (pin "1") (pinfunction "1_1") (pintype "unspecified"))
      (node (ref "Q1") (pin "6") (pinfunction "C_6") (pintype "unspecified"))
      (node (ref "SW2") (pin "2") (pinfunction "2_2") (pintype "unspecified"))
      (node (ref "U1") (pin "1") (pinfunction "RST_1") (pintype "unspecified"))
    )
    (net (code "56") (name "RTS") (class "Default")
      (node (ref "Q1") (pin "1") (pinfunction "E_1") (pintype "unspecified"))
      (node (ref "Q1") (pin "5") (pinfunction "B_5") (pintype "unspecified"))
      (node (ref "U4") (pin "14") (pinfunction "RTS#_14") (pintype "unspecified"))
    )
    (net (code "57") (name "RX") (class "Default")
      (node (ref "U1") (pin "15") (pinfunction "RXD0_15") (pintype "unspecified"))
      (node (ref "U4") (pin "2") (pinfunction "TXD_2") (pintype "unspecified"))
    )
    (net (code "58") (name "SC0") (class "Default")
      (node (ref "R2") (pin "2") (pinfunction "2_2") (pintype "unspecified"))
      (node (ref "RJ1") (pin "3") (pinfunction "3_3") (pintype "unspecified"))
      (node (ref "U2") (pin "5") (pinfunction "SC0_5") (pintype "unspecified"))
      (node (ref "U9") (pin "5") (pinfunction "BUS2_5") (pintype "unspecified"))
    )
    (net (code "59") (name "SC1") (class "Default")
      (node (ref "R25") (pin "2") (pinfunction "2_2") (pintype "unspecified"))
      (node (ref "RJ2") (pin "6") (pinfunction "6_6") (pintype "unspecified"))
      (node (ref "U10") (pin "5") (pinfunction "BUS2_5") (pintype "unspecified"))
      (node (ref "U2") (pin "7") (pinfunction "SC1_7") (pintype "unspecified"))
    )
    (net (code "60") (name "SC2") (class "Default")
      (node (ref "R27") (pin "2") (pinfunction "2_2") (pintype "unspecified"))
      (node (ref "RJ4") (pin "6") (pinfunction "6_6") (pintype "unspecified"))
      (node (ref "U11") (pin "5") (pinfunction "BUS2_5") (pintype "unspecified"))
      (node (ref "U2") (pin "9") (pinfunction "SC2_9") (pintype "unspecified"))
    )
    (net (code "61") (name "SC3") (class "Default")
      (node (ref "R29") (pin "2") (pinfunction "2_2") (pintype "unspecified"))
      (node (ref "RJ3") (pin "6") (pinfunction "6_6") (pintype "unspecified"))
      (node (ref "U12") (pin "5") (pinfunction "BUS2_5") (pintype "unspecified"))
      (node (ref "U2") (pin "11") (pinfunction "SC3_11") (pintype "unspecified"))
    )
    (net (code "62") (name "SC4") (class "Default")
      (node (ref "R31") (pin "2") (pinfunction "2_2") (pintype "unspecified"))
      (node (ref "RJ8") (pin "6") (pinfunction "6_6") (pintype "unspecified"))
      (node (ref "U13") (pin "5") (pinfunction "BUS2_5") (pintype "unspecified"))
      (node (ref "U2") (pin "14") (pinfunction "SC4_14") (pintype "unspecified"))
    )
    (net (code "63") (name "SC5") (class "Default")
      (node (ref "R33") (pin "2") (pinfunction "2_2") (pintype "unspecified"))
      (node (ref "RJ7") (pin "6") (pinfunction "6_6") (pintype "unspecified"))
      (node (ref "U14") (pin "5") (pinfunction "BUS2_5") (pintype "unspecified"))
      (node (ref "U2") (pin "16") (pinfunction "SC5_16") (pintype "unspecified"))
    )
    (net (code "64") (name "SC6") (class "Default")
      (node (ref "R35") (pin "2") (pinfunction "2_2") (pintype "unspecified"))
      (node (ref "RJ5") (pin "6") (pinfunction "6_6") (pintype "unspecified"))
      (node (ref "U15") (pin "5") (pinfunction "BUS2_5") (pintype "unspecified"))
      (node (ref "U2") (pin "18") (pinfunction "SC6_18") (pintype "unspecified"))
    )
    (net (code "65") (name "SC7") (class "Default")
      (node (ref "R37") (pin "2") (pinfunction "2_2") (pintype "unspecified"))
      (node (ref "RJ6") (pin "6") (pinfunction "6_6") (pintype "unspecified"))
      (node (ref "U16") (pin "5") (pinfunction "BUS2_5") (pintype "unspecified"))
      (node (ref "U2") (pin "20") (pinfunction "SC7_20") (pintype "unspecified"))
    )
    (net (code "66") (name "SCL") (class "Default")
      (node (ref "J1") (pin "3") (pinfunction "3_3") (pintype "unspecified"))
      (node (ref "R10") (pin "2") (pinfunction "2_2") (pintype "unspecified"))
      (node (ref "R18") (pin "1") (pinfunction "1_1") (pintype "unspecified"))
      (node (ref "U1") (pin "14") (pinfunction "GPIO5_14") (pintype "unspecified"))
      (node (ref "U2") (pin "22") (pinfunction "SCL_22") (pintype "unspecified"))
      (node (ref "U3") (pin "5") (pinfunction "BUS2_5") (pintype "unspecified"))
      (node (ref "U5") (pin "8") (pinfunction "SCK_8") (pintype "unspecified"))
    )
    (net (code "67") (name "SD0") (class "Default")
      (node (ref "R23") (pin "2") (pinfunction "2_2") (pintype "unspecified"))
      (node (ref "RJ1") (pin "6") (pinfunction "6_6") (pintype "unspecified"))
      (node (ref "U2") (pin "4") (pinfunction "SD0_4") (pintype "unspecified"))
      (node (ref "U9") (pin "4") (pinfunction "BUS1_4") (pintype "unspecified"))
    )
    (net (code "68") (name "SD1") (class "Default")
      (node (ref "R24") (pin "2") (pinfunction "2_2") (pintype "unspecified"))
      (node (ref "RJ2") (pin "3") (pinfunction "3_3") (pintype "unspecified"))
      (node (ref "U10") (pin "4") (pinfunction "BUS1_4") (pintype "unspecified"))
      (node (ref "U2") (pin "6") (pinfunction "SD1_6") (pintype "unspecified"))
    )
    (net (code "69") (name "SD2") (class "Default")
      (node (ref "R26") (pin "2") (pinfunction "2_2") (pintype "unspecified"))
      (node (ref "RJ4") (pin "3") (pinfunction "3_3") (pintype "unspecified"))
      (node (ref "U11") (pin "4") (pinfunction "BUS1_4") (pintype "unspecified"))
      (node (ref "U2") (pin "8") (pinfunction "SD2_8") (pintype "unspecified"))
    )
    (net (code "70") (name "SD3") (class "Default")
      (node (ref "R28") (pin "2") (pinfunction "2_2") (pintype "unspecified"))
      (node (ref "RJ3") (pin "3") (pinfunction "3_3") (pintype "unspecified"))
      (node (ref "U12") (pin "4") (pinfunction "BUS1_4") (pintype "unspecified"))
      (node (ref "U2") (pin "10") (pinfunction "SD3_10") (pintype "unspecified"))
    )
    (net (code "71") (name "SD4") (class "Default")
      (node (ref "R30") (pin "2") (pinfunction "2_2") (pintype "unspecified"))
      (node (ref "RJ8") (pin "3") (pinfunction "3_3") (pintype "unspecified"))
      (node (ref "U13") (pin "4") (pinfunction "BUS1_4") (pintype "unspecified"))
      (node (ref "U2") (pin "13") (pinfunction "SD4_13") (pintype "unspecified"))
    )
    (net (code "72") (name "SD5") (class "Default")
      (node (ref "R32") (pin "2") (pinfunction "2_2") (pintype "unspecified"))
      (node (ref "RJ7") (pin "3") (pinfunction "3_3") (pintype "unspecified"))
      (node (ref "U14") (pin "4") (pinfunction "BUS1_4") (pintype "unspecified"))
      (node (ref "U2") (pin "15") (pinfunction "SD5_15") (pintype "unspecified"))
    )
    (net (code "73") (name "SD6") (class "Default")
      (node (ref "R34") (pin "2") (pinfunction "2_2") (pintype "unspecified"))
      (node (ref "RJ5") (pin "3") (pinfunction "3_3") (pintype "unspecified"))
      (node (ref "U15") (pin "4") (pinfunction "BUS1_4") (pintype "unspecified"))
      (node (ref "U2") (pin "17") (pinfunction "SD6_17") (pintype "unspecified"))
    )
    (net (code "74") (name "SD7") (class "Default")
      (node (ref "R36") (pin "2") (pinfunction "2_2") (pintype "unspecified"))
      (node (ref "RJ6") (pin "3") (pinfunction "3_3") (pintype "unspecified"))
      (node (ref "U16") (pin "4") (pinfunction "BUS1_4") (pintype "unspecified"))
      (node (ref "U2") (pin "19") (pinfunction "SD7_19") (pintype "unspecified"))
    )
    (net (code "75") (name "SDA") (class "Default")
      (node (ref "J1") (pin "4") (pinfunction "4_4") (pintype "unspecified"))
      (node (ref "R12") (pin "2") (pinfunction "2_2") (pintype "unspecified"))
      (node (ref "R17") (pin "2") (pinfunction "2_2") (pintype "unspecified"))
      (node (ref "U1") (pin "13") (pinfunction "GPIO4_13") (pintype "unspecified"))
      (node (ref "U2") (pin "23") (pinfunction "SDA_23") (pintype "unspecified"))
      (node (ref "U3") (pin "4") (pinfunction "BUS1_4") (pintype "unspecified"))
      (node (ref "U5") (pin "9") (pinfunction "SDA_9") (pintype "unspecified"))
    )
    (net (code "76") (name "TX") (class "Default")
      (node (ref "R21") (pin "1") (pinfunction "1_1") (pintype "unspecified"))
      (node (ref "U1") (pin "16") (pinfunction "TXD0_16") (pintype "unspecified"))
    )
    (net (code "77") (name "unconnected-(Q2-D12-Pad2)") (class "Default")
      (node (ref "Q2") (pin "2") (pinfunction "D12_2") (pintype "unspecified+no_connect"))
    )
    (net (code "78") (name "unconnected-(Q2-D12-Pad5)") (class "Default")
      (node (ref "Q2") (pin "5") (pinfunction "D12_5") (pintype "unspecified+no_connect"))
    )
    (net (code "79") (name "unconnected-(Q3-NC-Pad4)") (class "Default")
      (node (ref "Q3") (pin "4") (pinfunction "NC_4") (pintype "unspecified+no_connect"))
    )
    (net (code "80") (name "unconnected-(RJ1-Pad2)") (class "Default")
      (node (ref "RJ1") (pin "2") (pinfunction "2_2") (pintype "unspecified+no_connect"))
    )
    (net (code "81") (name "unconnected-(RJ1-Pad7)") (class "Default")
      (node (ref "RJ1") (pin "7") (pinfunction "7_7") (pintype "unspecified+no_connect"))
    )
    (net (code "82") (name "unconnected-(RJ2-Pad2)") (class "Default")
      (node (ref "RJ2") (pin "2") (pinfunction "2_2") (pintype "unspecified+no_connect"))
    )
    (net (code "83") (name "unconnected-(RJ2-Pad7)") (class "Default")
      (node (ref "RJ2") (pin "7") (pinfunction "7_7") (pintype "unspecified+no_connect"))
    )
    (net (code "84") (name "unconnected-(RJ3-Pad2)") (class "Default")
      (node (ref "RJ3") (pin "2") (pinfunction "2_2") (pintype "unspecified+no_connect"))
    )
    (net (code "85") (name "unconnected-(RJ3-Pad5)") (class "Default")
      (node (ref "RJ3") (pin "5") (pinfunction "5_5") (pintype "unspecified+no_connect"))
    )
    (net (code "86") (name "unconnected-(RJ3-Pad7)") (class "Default")
      (node (ref "RJ3") (pin "7") (pinfunction "7_7") (pintype "unspecified+no_connect"))
    )
    (net (code "87") (name "unconnected-(RJ4-Pad2)") (class "Default")
      (node (ref "RJ4") (pin "2") (pinfunction "2_2") (pintype "unspecified+no_connect"))
    )
    (net (code "88") (name "unconnected-(RJ4-Pad7)") (class "Default")
      (node (ref "RJ4") (pin "7") (pinfunction "7_7") (pintype "unspecified+no_connect"))
    )
    (net (code "89") (name "unconnected-(RJ5-Pad2)") (class "Default")
      (node (ref "RJ5") (pin "2") (pinfunction "2_2") (pintype "unspecified+no_connect"))
    )
    (net (code "90") (name "unconnected-(RJ5-Pad7)") (class "Default")
      (node (ref "RJ5") (pin "7") (pinfunction "7_7") (pintype "unspecified+no_connect"))
    )
    (net (code "91") (name "unconnected-(RJ6-Pad2)") (class "Default")
      (node (ref "RJ6") (pin "2") (pinfunction "2_2") (pintype "unspecified+no_connect"))
    )
    (net (code "92") (name "unconnected-(RJ6-Pad7)") (class "Default")
      (node (ref "RJ6") (pin "7") (pinfunction "7_7") (pintype "unspecified+no_connect"))
    )
    (net (code "93") (name "unconnected-(RJ7-Pad2)") (class "Default")
      (node (ref "RJ7") (pin "2") (pinfunction "2_2") (pintype "unspecified+no_connect"))
    )
    (net (code "94") (name "unconnected-(RJ7-Pad7)") (class "Default")
      (node (ref "RJ7") (pin "7") (pinfunction "7_7") (pintype "unspecified+no_connect"))
    )
    (net (code "95") (name "unconnected-(RJ8-Pad2)") (class "Default")
      (node (ref "RJ8") (pin "2") (pinfunction "2_2") (pintype "unspecified+no_connect"))
    )
    (net (code "96") (name "unconnected-(RJ8-Pad7)") (class "Default")
      (node (ref "RJ8") (pin "7") (pinfunction "7_7") (pintype "unspecified+no_connect"))
    )
    (net (code "97") (name "unconnected-(SW2-Pad1)") (class "Default")
      (node (ref "SW2") (pin "1") (pinfunction "1_1") (pintype "unspecified+no_connect"))
    )
    (net (code "98") (name "unconnected-(SW2-Pad4)") (class "Default")
      (node (ref "SW2") (pin "4") (pinfunction "4_4") (pintype "unspecified+no_connect"))
    )
    (net (code "99") (name "unconnected-(U1-CS0-Pad17)") (class "Default")
      (node (ref "U1") (pin "17") (pinfunction "CS0_17") (pintype "unspecified+no_connect"))
    )
    (net (code "100") (name "unconnected-(U1-GPIO9-Pad19)") (class "Default")
      (node (ref "U1") (pin "19") (pinfunction "GPIO9_19") (pintype "unspecified+no_connect"))
    )
    (net (code "101") (name "unconnected-(U1-GPIO10-Pad20)") (class "Default")
      (node (ref "U1") (pin "20") (pinfunction "GPIO10_20") (pintype "unspecified+no_connect"))
    )
    (net (code "102") (name "unconnected-(U1-GPIO16-Pad4)") (class "Default")
      (node (ref "U1") (pin "4") (pinfunction "GPIO16_4") (pintype "unspecified+no_connect"))
    )
    (net (code "103") (name "unconnected-(U1-MISO-Pad18)") (class "Default")
      (node (ref "U1") (pin "18") (pinfunction "MISO_18") (pintype "unspecified+no_connect"))
    )
    (net (code "104") (name "unconnected-(U1-MOSI-Pad21)") (class "Default")
      (node (ref "U1") (pin "21") (pinfunction "MOSI_21") (pintype "unspecified+no_connect"))
    )
    (net (code "105") (name "unconnected-(U1-SCLK-Pad22)") (class "Default")
      (node (ref "U1") (pin "22") (pinfunction "SCLK_22") (pintype "unspecified+no_connect"))
    )
    (net (code "106") (name "unconnected-(U3-NC-Pad2)") (class "Default")
      (node (ref "U3") (pin "2") (pinfunction "NC_2") (pintype "unspecified+no_connect"))
    )
    (net (code "107") (name "unconnected-(U4-CTS#-Pad9)") (class "Default")
      (node (ref "U4") (pin "9") (pinfunction "CTS#_9") (pintype "unspecified+no_connect"))
    )
    (net (code "108") (name "unconnected-(U4-DCD#-Pad12)") (class "Default")
      (node (ref "U4") (pin "12") (pinfunction "DCD#_12") (pintype "unspecified+no_connect"))
    )
    (net (code "109") (name "unconnected-(U4-DSR#-Pad10)") (class "Default")
      (node (ref "U4") (pin "10") (pinfunction "DSR#_10") (pintype "unspecified+no_connect"))
    )
    (net (code "110") (name "unconnected-(U4-NC.-Pad7)") (class "Default")
      (node (ref "U4") (pin "7") (pinfunction "NC._7") (pintype "unspecified+no_connect"))
    )
    (net (code "111") (name "unconnected-(U4-NC.-Pad8)") (class "Default")
      (node (ref "U4") (pin "8") (pinfunction "NC._8") (pintype "unspecified+no_connect"))
    )
    (net (code "112") (name "unconnected-(U4-R232-Pad15)") (class "Default")
      (node (ref "U4") (pin "15") (pinfunction "R232_15") (pintype "unspecified+no_connect"))
    )
    (net (code "113") (name "unconnected-(U4-RI#-Pad11)") (class "Default")
      (node (ref "U4") (pin "11") (pinfunction "RI#_11") (pintype "unspecified+no_connect"))
    )
    (net (code "114") (name "unconnected-(U5-NC-Pad7)") (class "Default")
      (node (ref "U5") (pin "7") (pinfunction "NC_7") (pintype "unspecified+no_connect"))
    )
    (net (code "115") (name "unconnected-(U5-NC-Pad10)") (class "Default")
      (node (ref "U5") (pin "10") (pinfunction "NC_10") (pintype "unspecified+no_connect"))
    )
    (net (code "116") (name "unconnected-(U6-TD-Pad4)") (class "Default")
      (node (ref "U6") (pin "4") (pinfunction "TD_4") (pintype "unspecified+no_connect"))
    )
    (net (code "117") (name "unconnected-(U8-EP-Pad9)") (class "Default")
      (node (ref "U8") (pin "9") (pinfunction "EP_9") (pintype "unspecified+no_connect"))
    )
    (net (code "118") (name "unconnected-(U9-NC-Pad2)") (class "Default")
      (node (ref "U9") (pin "2") (pinfunction "NC_2") (pintype "unspecified+no_connect"))
    )
    (net (code "119") (name "unconnected-(U10-NC-Pad2)") (class "Default")
      (node (ref "U10") (pin "2") (pinfunction "NC_2") (pintype "unspecified+no_connect"))
    )
    (net (code "120") (name "unconnected-(U11-NC-Pad2)") (class "Default")
      (node (ref "U11") (pin "2") (pinfunction "NC_2") (pintype "unspecified+no_connect"))
    )
    (net (code "121") (name "unconnected-(U12-NC-Pad2)") (class "Default")
      (node (ref "U12") (pin "2") (pinfunction "NC_2") (pintype "unspecified+no_connect"))
    )
    (net (code "122") (name "unconnected-(U13-NC-Pad2)") (class "Default")
      (node (ref "U13") (pin "2") (pinfunction "NC_2") (pintype "unspecified+no_connect"))
    )
    (net (code "123") (name "unconnected-(U14-NC-Pad2)") (class "Default")
      (node (ref "U14") (pin "2") (pinfunction "NC_2") (pintype "unspecified+no_connect"))
    )
    (net (code "124") (name "unconnected-(U15-NC-Pad2)") (class "Default")
      (node (ref "U15") (pin "2") (pinfunction "NC_2") (pintype "unspecified+no_connect"))
    )
    (net (code "125") (name "unconnected-(U16-NC-Pad2)") (class "Default")
      (node (ref "U16") (pin "2") (pinfunction "NC_2") (pintype "unspecified+no_connect"))
    )
    (net (code "126") (name "unconnected-(USB1-SBU1-PadA8)") (class "Default")
      (node (ref "USB1") (pin "A8") (pinfunction "SBU1_A8") (pintype "unspecified+no_connect"))
    )
    (net (code "127") (name "unconnected-(USB1-SBU2-PadB8)") (class "Default")
      (node (ref "USB1") (pin "B8") (pinfunction "SBU2_B8") (pintype "unspecified+no_connect"))
    )
  )
)
